# PocketBeagle.net
KiCad netlist of a schematic drawn in EAGLE
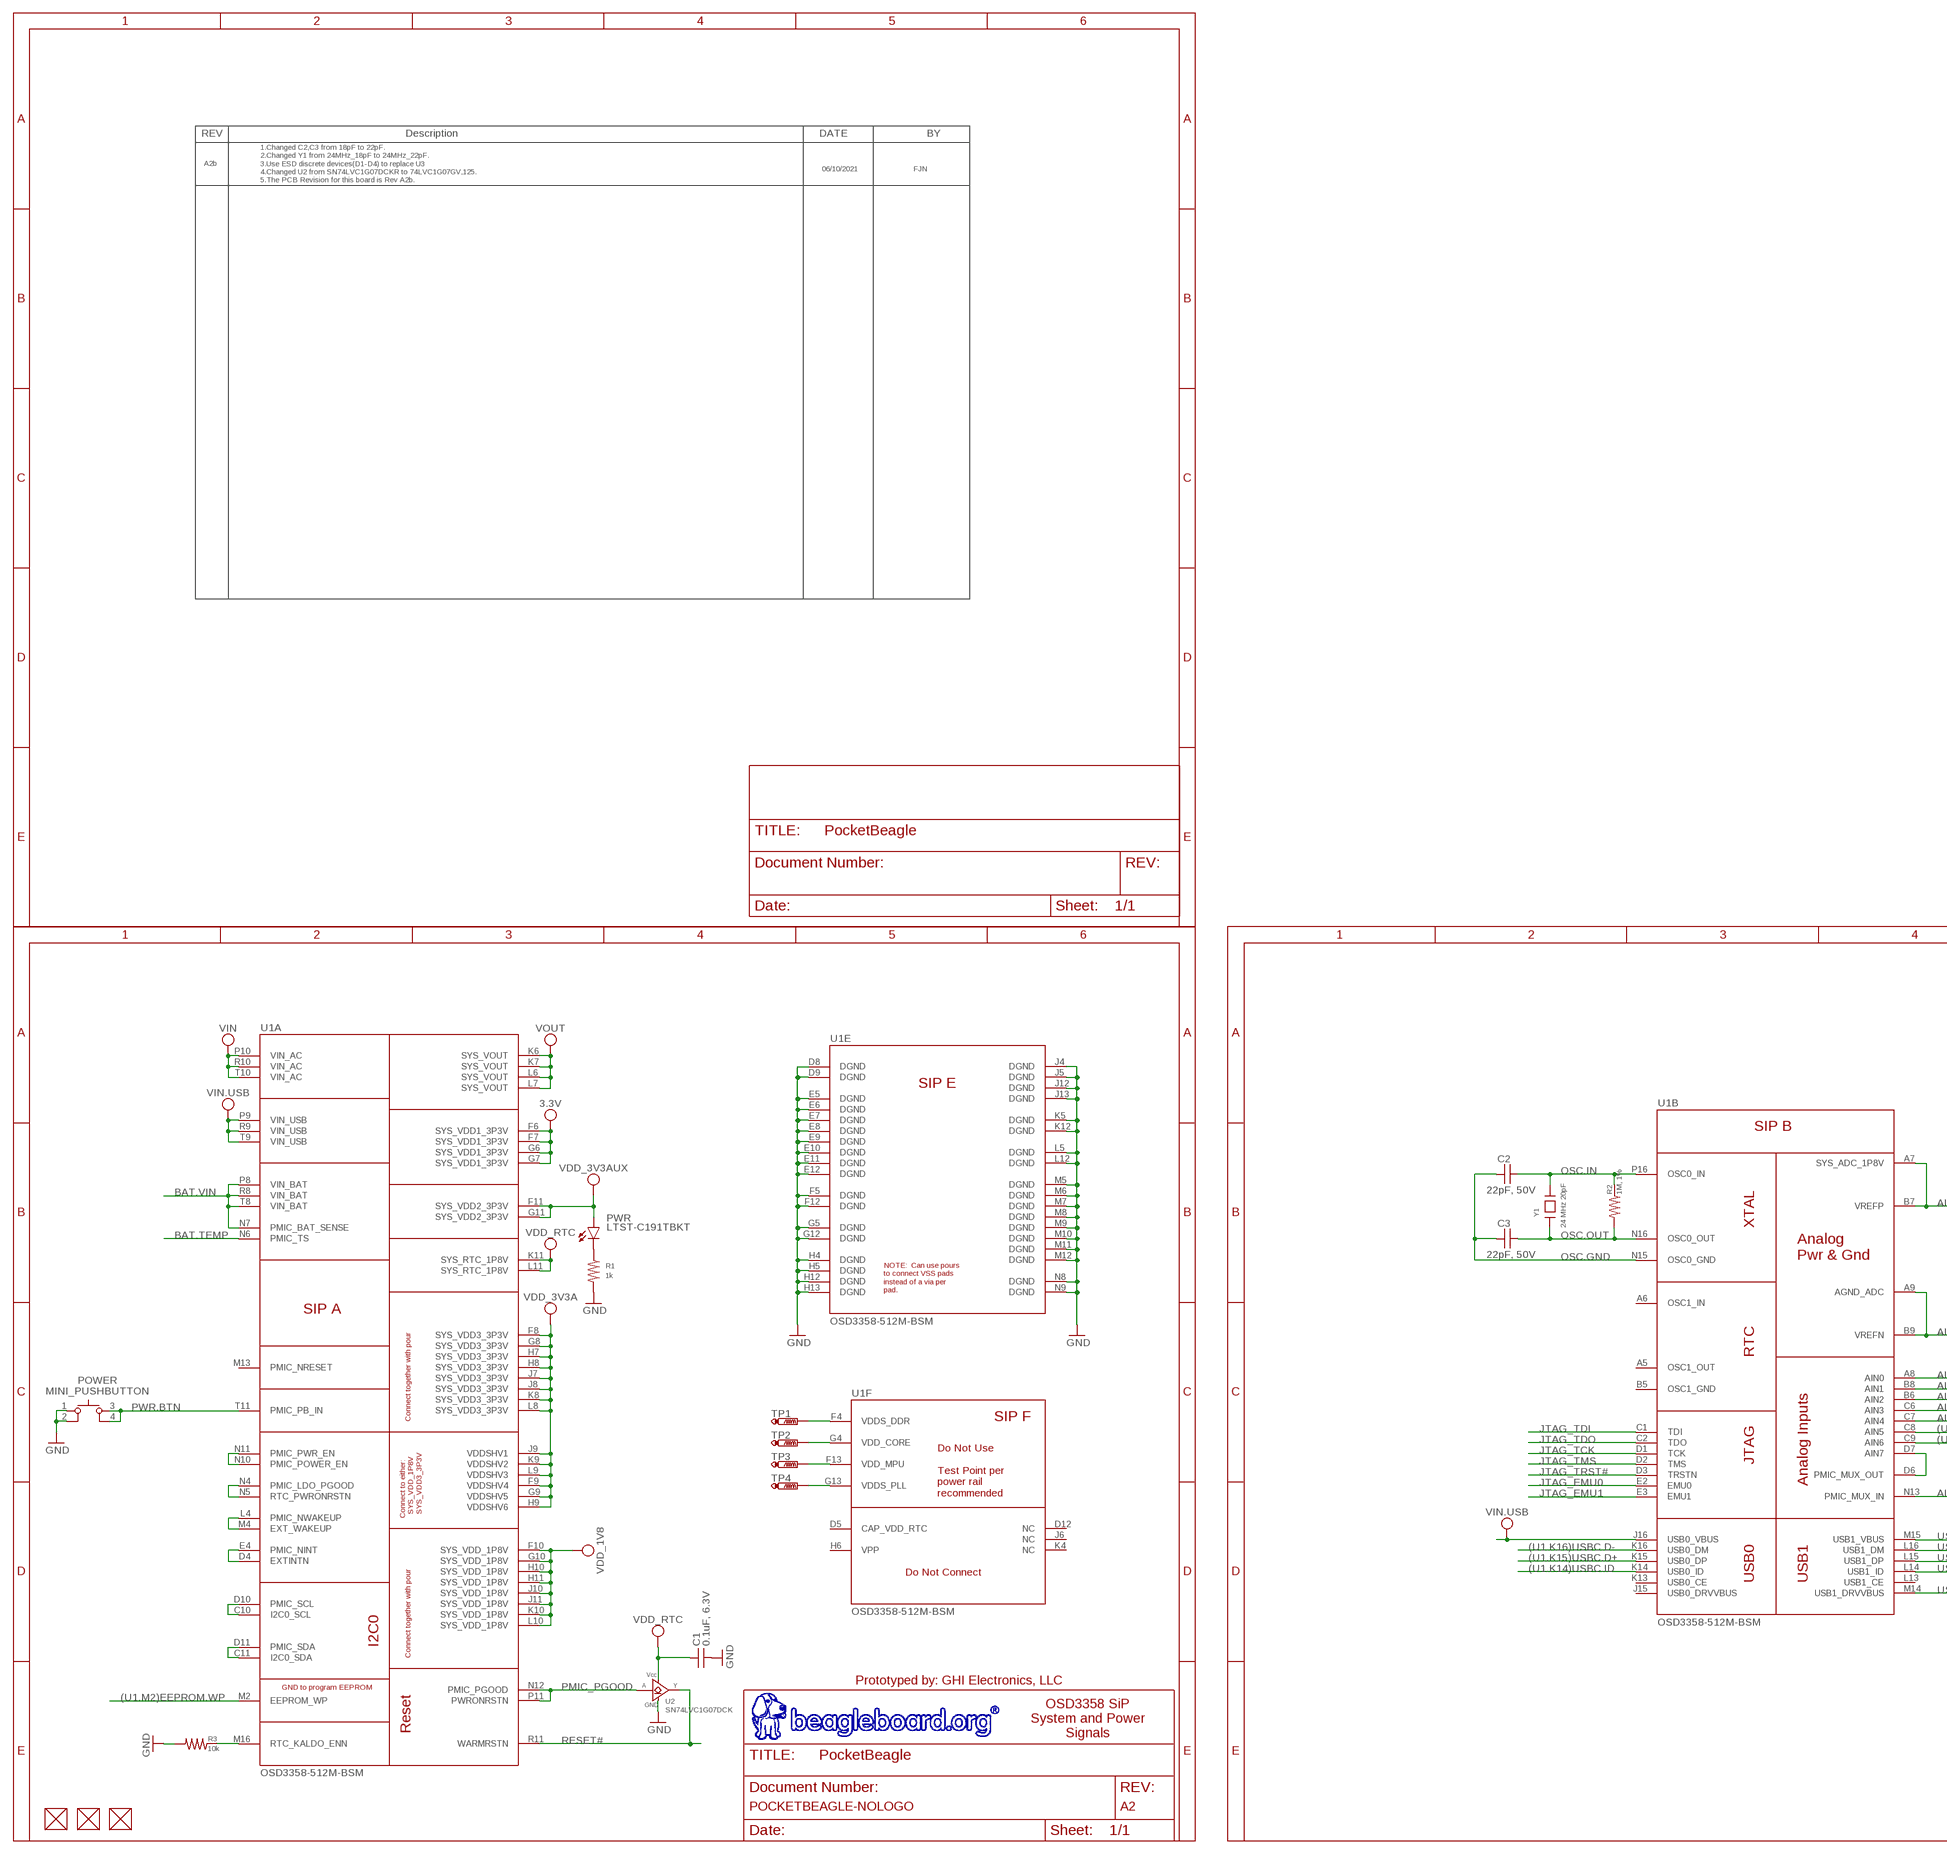
[diagram p0: schematic, sheet 1, part 1 of 3]
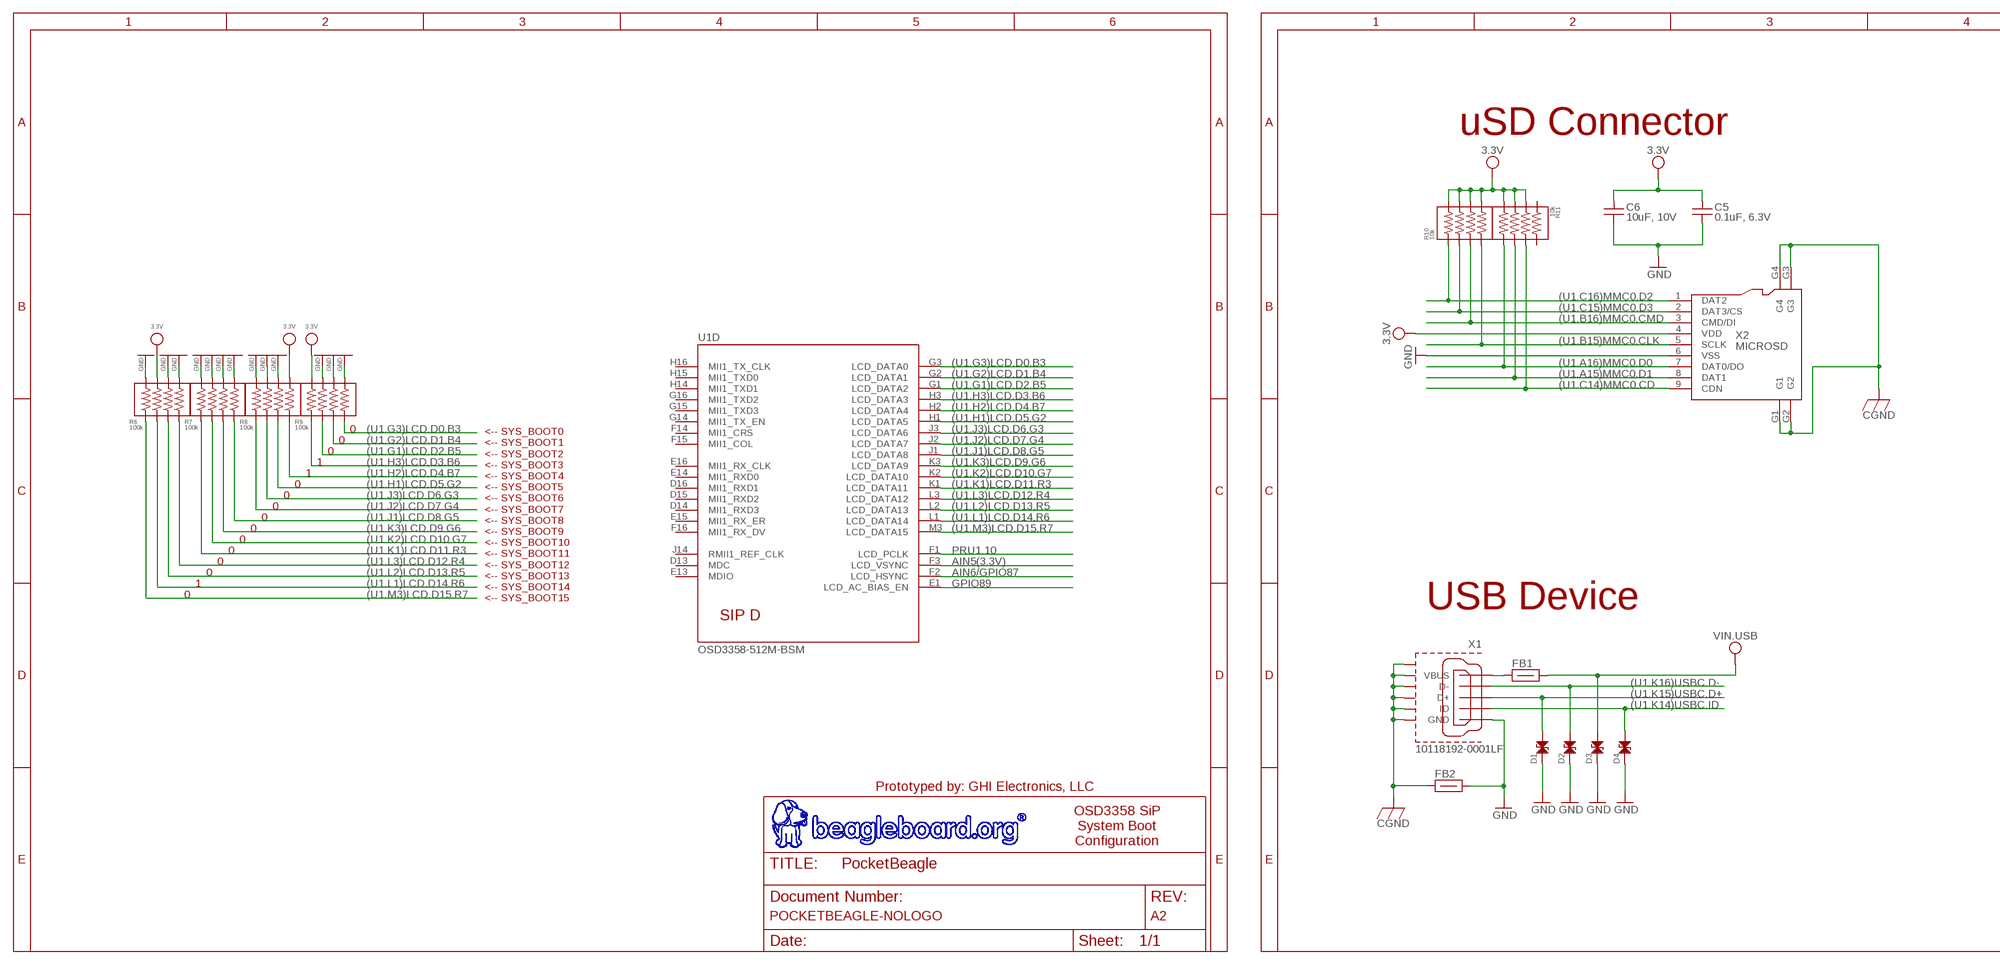
[diagram p1: schematic, sheet 1, part 2 of 3]
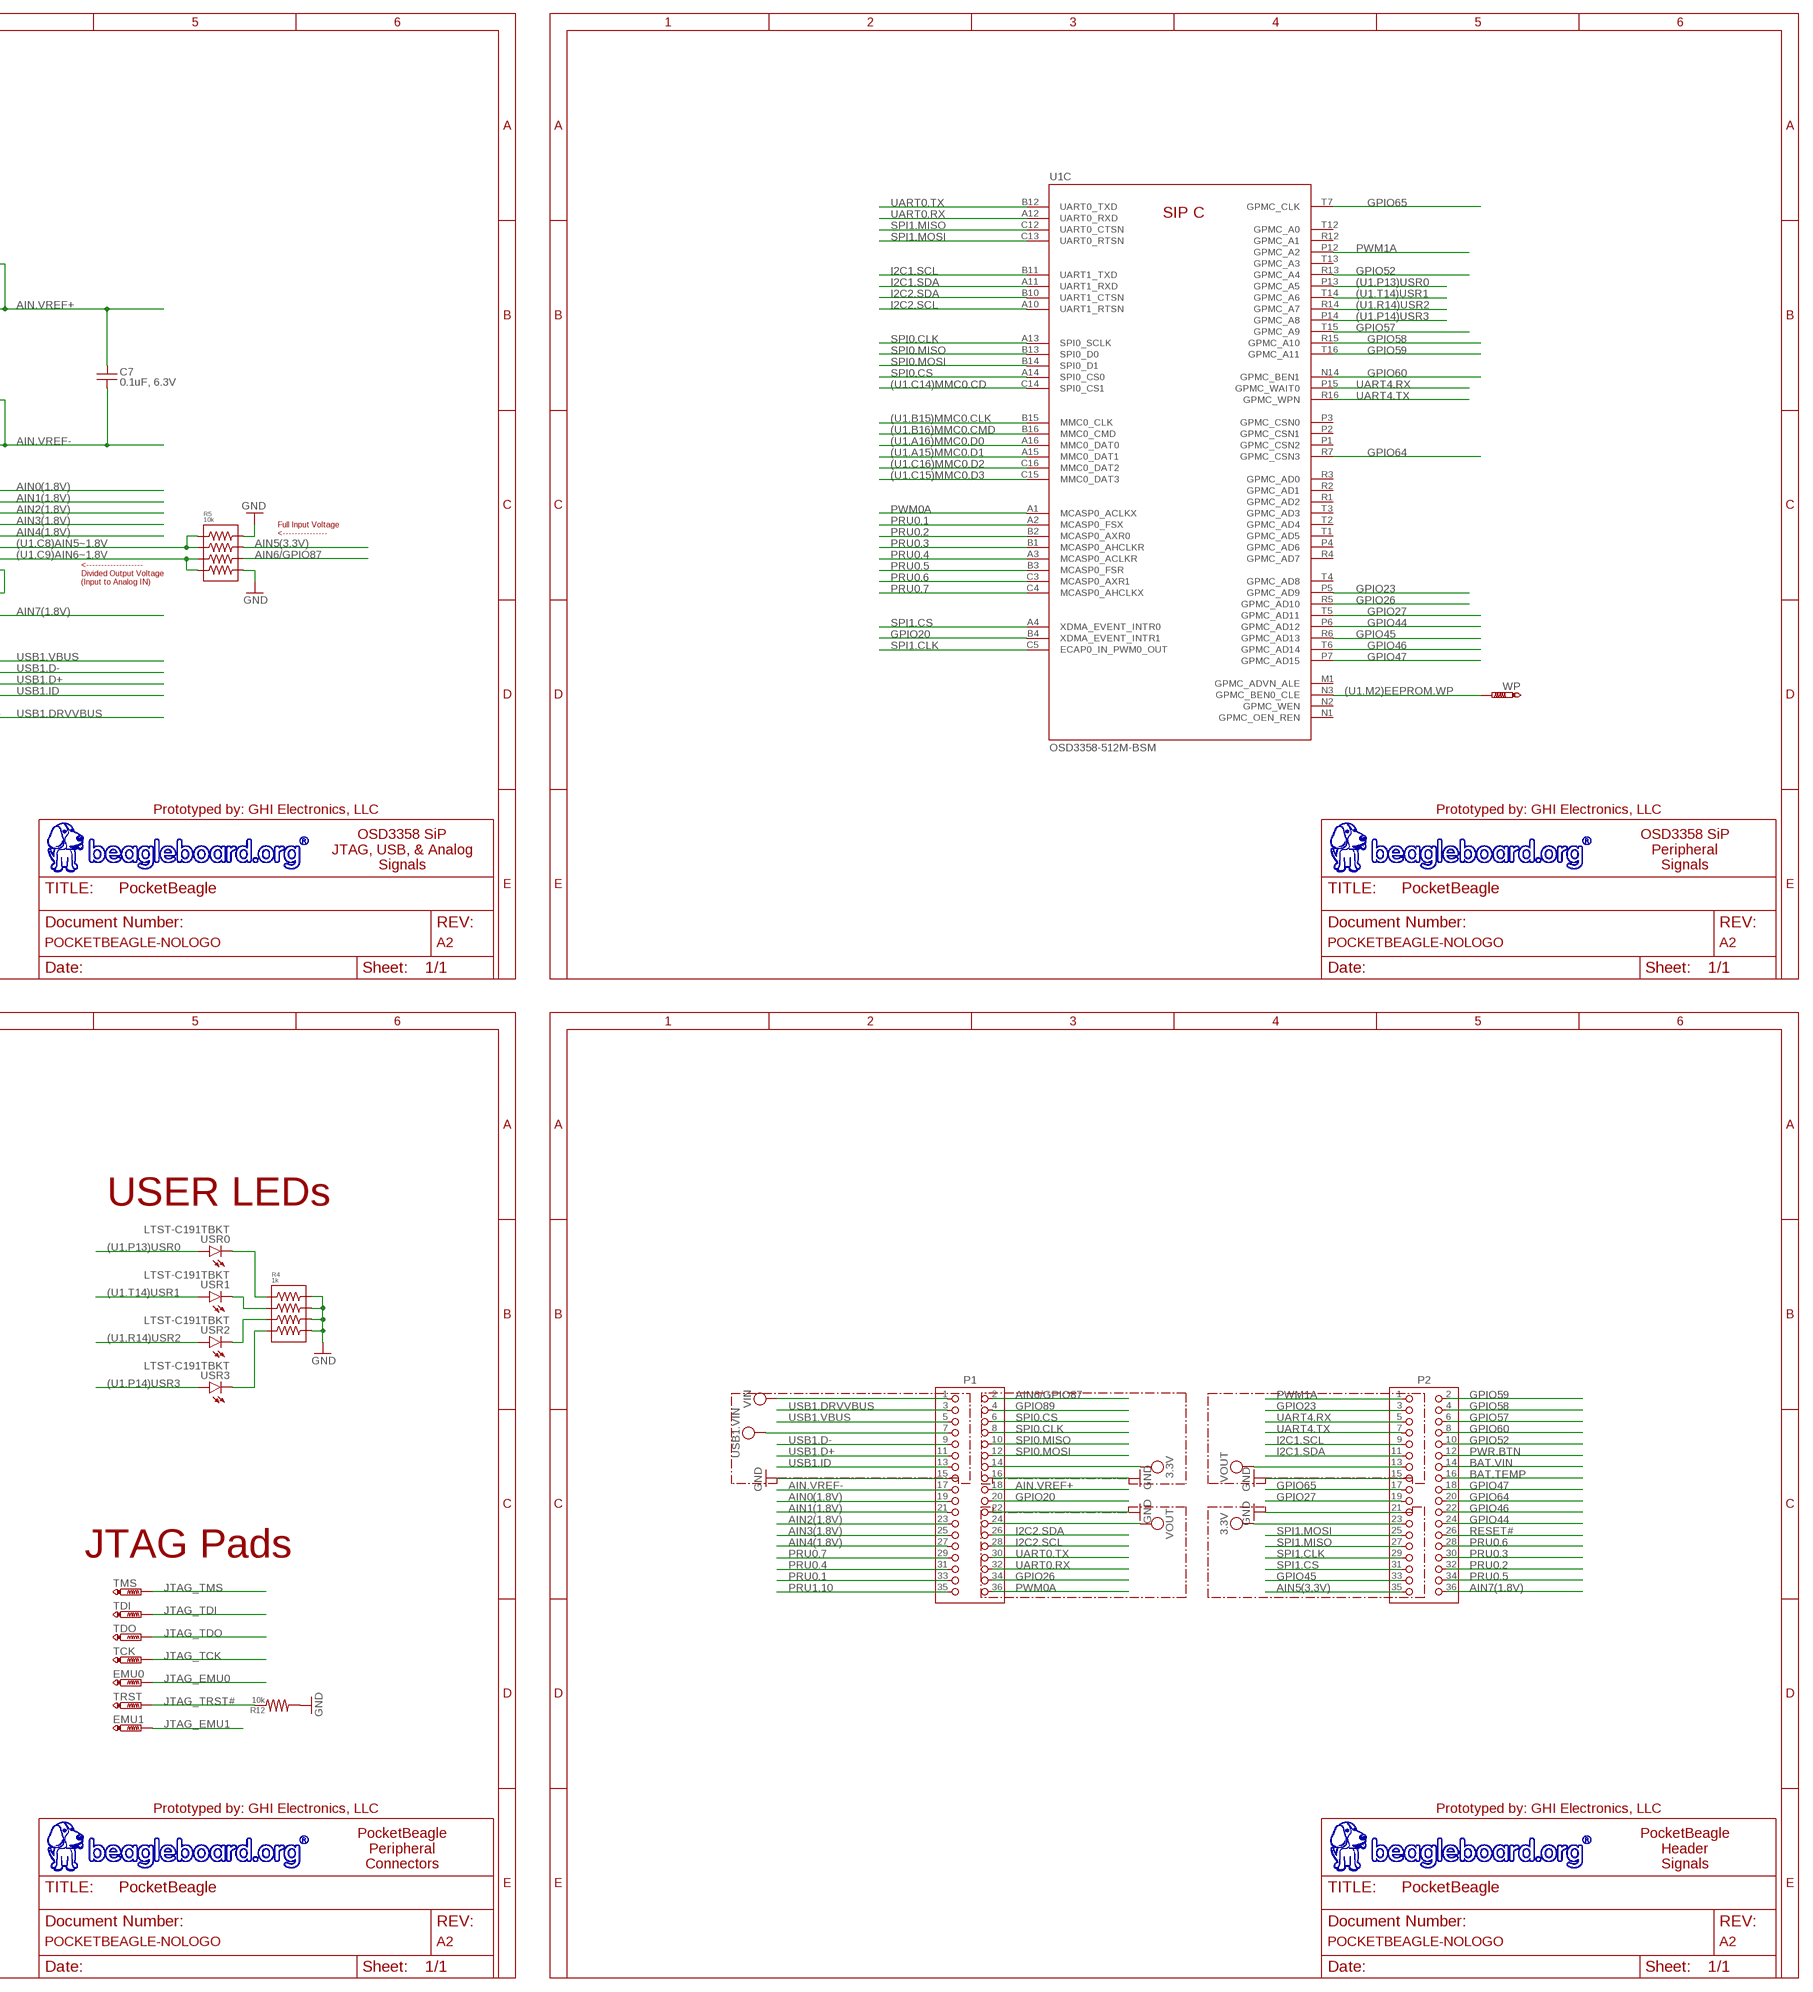
[diagram p2: schematic, sheet 1, part 3 of 3]

(export (version "E")
  (design (tool "Eeschema 10.0.6"))
  (components
    (comp (ref "C1")
      (value "0.1uF, 6.3V")
      (footprint "eagle-import:0402")
      (libsource (lib "eagle-import") (part "CAPACITOR-(INCH)-0402"))
    )
    (comp (ref "C2")
      (value "22pF, 50V")
      (footprint "eagle-import:0402")
      (libsource (lib "eagle-import") (part "CAPACITOR-(INCH)-0402"))
    )
    (comp (ref "C3")
      (value "22pF, 50V")
      (footprint "eagle-import:0402")
      (libsource (lib "eagle-import") (part "CAPACITOR-(INCH)-0402"))
    )
    (comp (ref "C5")
      (value "0.1uF, 6.3V")
      (footprint "eagle-import:0402")
      (libsource (lib "eagle-import") (part "CAPACITOR-(INCH)-0402"))
    )
    (comp (ref "C6")
      (value "10uF, 10V")
      (footprint "eagle-import:0603")
      (libsource (lib "eagle-import") (part "CAPACITOR-(INCH)-0603"))
    )
    (comp (ref "C7")
      (value "0.1uF, 6.3V")
      (footprint "eagle-import:0402")
      (libsource (lib "eagle-import") (part "CAPACITOR-(INCH)-0402"))
    )
    (comp (ref "D1")
      (value "D-ESD-2P-DOUBLE")
      (footprint "eagle-import:ESD-0402-NO-SILK")
      (libsource (lib "eagle-import") (part "D-ESD-2P-DOUBLE"))
    )
    (comp (ref "D2")
      (value "D-ESD-2P-DOUBLE")
      (footprint "eagle-import:ESD-0402-NO-SILK")
      (libsource (lib "eagle-import") (part "D-ESD-2P-DOUBLE"))
    )
    (comp (ref "D3")
      (value "D-ESD-2P-DOUBLE")
      (footprint "eagle-import:ESD-0402-NO-SILK")
      (libsource (lib "eagle-import") (part "D-ESD-2P-DOUBLE"))
    )
    (comp (ref "D4")
      (value "D-ESD-2P-DOUBLE")
      (footprint "eagle-import:ESD-0402-NO-SILK")
      (libsource (lib "eagle-import") (part "D-ESD-2P-DOUBLE"))
    )
    (comp (ref "EMU0")
      (value "PTR1B1,27")
      (footprint "eagle-import:B1,27")
      (libsource (lib "eagle-import") (part "PTR1B1,27"))
    )
    (comp (ref "EMU1")
      (value "PTR1B1,27")
      (footprint "eagle-import:B1,27")
      (libsource (lib "eagle-import") (part "PTR1B1,27"))
    )
    (comp (ref "FB1")
      (value "FB-(INCH)-0603")
      (footprint "eagle-import:0603")
      (libsource (lib "eagle-import") (part "FB-(INCH)-0603"))
    )
    (comp (ref "FB2")
      (value "FB-(INCH)-0603")
      (footprint "eagle-import:0603")
      (libsource (lib "eagle-import") (part "FB-(INCH)-0603"))
    )
    (comp (ref "FUD1")
      (value "FIDUCIAL")
      (footprint "eagle-import:FIDUCIAL_40MIL")
      (libsource (lib "eagle-import") (part "FIDUCIAL"))
    )
    (comp (ref "FUD2")
      (value "FIDUCIAL")
      (footprint "eagle-import:FIDUCIAL_40MIL")
      (libsource (lib "eagle-import") (part "FIDUCIAL"))
    )
    (comp (ref "FUD3")
      (value "FIDUCIAL")
      (footprint "eagle-import:FIDUCIAL_40MIL")
      (libsource (lib "eagle-import") (part "FIDUCIAL"))
    )
    (comp (ref "P1")
      (value "2X18-(INCH)-0.1-TH-(35MIL-DIA)-W/O-SILK")
      (footprint "eagle-import:TH-2X18-(35MIL-DIA)-W_O-SILK")
      (libsource (lib "eagle-import") (part "2X18-(INCH)-0.1-TH-(35MIL-DIA)-W/O-SILK"))
    )
    (comp (ref "P2")
      (value "2X18-(INCH)-0.1-TH-(35MIL-DIA)-W/O-SILK")
      (footprint "eagle-import:TH-2X18-(35MIL-DIA)-W_O-SILK")
      (libsource (lib "eagle-import") (part "2X18-(INCH)-0.1-TH-(35MIL-DIA)-W/O-SILK"))
    )
    (comp (ref "POWER")
      (value "MINI_PUSHBUTTON")
      (footprint "eagle-import:MINI_PUSHBUTTON")
      (libsource (lib "eagle-import") (part "MINI_PUSHBUTTON"))
    )
    (comp (ref "PWR")
      (value "LTST-C191TBKT")
      (footprint "eagle-import:0603-LED")
      (libsource (lib "eagle-import") (part "LED-(INCH)-0603"))
    )
    (comp (ref "R1")
      (value "1k")
      (footprint "eagle-import:0402")
      (libsource (lib "eagle-import") (part "RESISTOR-(INCH)-0402"))
    )
    (comp (ref "R2")
      (value "1M, 1%")
      (footprint "eagle-import:0402")
      (libsource (lib "eagle-import") (part "RESISTOR-(INCH)-0402"))
    )
    (comp (ref "R3")
      (value "10k")
      (footprint "eagle-import:0402")
      (libsource (lib "eagle-import") (part "RESISTOR-(INCH)-0402"))
    )
    (comp (ref "R4")
      (value "1k")
      (footprint "eagle-import:RN0804")
      (libsource (lib "eagle-import") (part "RESISTOR.NETWORK-(4)"))
    )
    (comp (ref "R5")
      (value "10k")
      (footprint "eagle-import:RN0804")
      (libsource (lib "eagle-import") (part "RESISTOR.NETWORK-(4)"))
    )
    (comp (ref "R6")
      (value "100k")
      (footprint "eagle-import:RN0804")
      (libsource (lib "eagle-import") (part "RESISTOR.NETWORK-(4)"))
    )
    (comp (ref "R7")
      (value "100k")
      (footprint "eagle-import:RN0804")
      (libsource (lib "eagle-import") (part "RESISTOR.NETWORK-(4)"))
    )
    (comp (ref "R8")
      (value "100k")
      (footprint "eagle-import:RN0804")
      (libsource (lib "eagle-import") (part "RESISTOR.NETWORK-(4)"))
    )
    (comp (ref "R9")
      (value "100k")
      (footprint "eagle-import:RN0804")
      (libsource (lib "eagle-import") (part "RESISTOR.NETWORK-(4)"))
    )
    (comp (ref "R10")
      (value "10k")
      (footprint "eagle-import:RN0804")
      (libsource (lib "eagle-import") (part "RESISTOR.NETWORK-(4)"))
    )
    (comp (ref "R11")
      (value "10k")
      (footprint "eagle-import:RN0804")
      (libsource (lib "eagle-import") (part "RESISTOR.NETWORK-(4)"))
    )
    (comp (ref "R12")
      (value "10k")
      (footprint "eagle-import:0402")
      (libsource (lib "eagle-import") (part "RESISTOR-(INCH)-0402"))
    )
    (comp (ref "TCK")
      (value "PTR1B1,27")
      (footprint "eagle-import:B1,27")
      (libsource (lib "eagle-import") (part "PTR1B1,27"))
    )
    (comp (ref "TDI")
      (value "PTR1B1,27")
      (footprint "eagle-import:B1,27")
      (libsource (lib "eagle-import") (part "PTR1B1,27"))
    )
    (comp (ref "TDO")
      (value "PTR1B1,27")
      (footprint "eagle-import:B1,27")
      (libsource (lib "eagle-import") (part "PTR1B1,27"))
    )
    (comp (ref "TMS")
      (value "PTR1B1,27")
      (footprint "eagle-import:B1,27")
      (libsource (lib "eagle-import") (part "PTR1B1,27"))
    )
    (comp (ref "TP1")
      (value "PTR1B1,27")
      (footprint "eagle-import:B1,27")
      (libsource (lib "eagle-import") (part "PTR1B1,27"))
    )
    (comp (ref "TP2")
      (value "PTR1B1,27")
      (footprint "eagle-import:B1,27")
      (libsource (lib "eagle-import") (part "PTR1B1,27"))
    )
    (comp (ref "TP3")
      (value "PTR1B1,27")
      (footprint "eagle-import:B1,27")
      (libsource (lib "eagle-import") (part "PTR1B1,27"))
    )
    (comp (ref "TP4")
      (value "PTR1B1,27")
      (footprint "eagle-import:B1,27")
      (libsource (lib "eagle-import") (part "PTR1B1,27"))
    )
    (comp (ref "TRST")
      (value "PTR1B1,27")
      (footprint "eagle-import:B1,27")
      (libsource (lib "eagle-import") (part "PTR1B1,27"))
    )
    (comp (ref "U1")
      (value "OSD3358-512M-BSM")
      (footprint "eagle-import:OSD335X-BGA-256")
      (libsource (lib "eagle-import") (part "OSD3358-512M-BSM"))
    )
    (comp (ref "U2")
      (value "SN74LVC1G07DCK")
      (footprint "eagle-import:SC70(TI-DCK)")
      (libsource (lib "eagle-import") (part "SN74LVC1G07DCK"))
    )
    (comp (ref "USR0")
      (value "LTST-C191TBKT")
      (footprint "eagle-import:0603-LED")
      (libsource (lib "eagle-import") (part "LED-(INCH)-0603"))
    )
    (comp (ref "USR1")
      (value "LTST-C191TBKT")
      (footprint "eagle-import:0603-LED")
      (libsource (lib "eagle-import") (part "LED-(INCH)-0603"))
    )
    (comp (ref "USR2")
      (value "LTST-C191TBKT")
      (footprint "eagle-import:0603-LED")
      (libsource (lib "eagle-import") (part "LED-(INCH)-0603"))
    )
    (comp (ref "USR3")
      (value "LTST-C191TBKT")
      (footprint "eagle-import:0603-LED")
      (libsource (lib "eagle-import") (part "LED-(INCH)-0603"))
    )
    (comp (ref "WP")
      (value "PTR1B1,27")
      (footprint "eagle-import:B1,27")
      (libsource (lib "eagle-import") (part "PTR1B1,27"))
    )
    (comp (ref "X1")
      (value "10118192-0001LF")
      (footprint "eagle-import:10118192-0001LF(MICRO-USB-B-AMPHENOL-FCI)")
      (libsource (lib "eagle-import") (part "10118192-0001LF"))
    )
    (comp (ref "X2")
      (value "MICROSD")
      (footprint "eagle-import:MICROSD")
      (libsource (lib "eagle-import") (part "MICROSD"))
    )
    (comp (ref "Y1")
      (value "24 MHz 20pF")
      (footprint "eagle-import:CRYSTAL_5X3.2MM")
      (libsource (lib "eagle-import") (part "CRYSTAL_5X3.2MM"))
    )
  )
  (nets
    (net (code "1") (name "/(U1.A15)MMC0.D1") (class "Default")
      (node (ref "R11") (pin "6") (pinfunction "6_6") (pintype "bidirectional"))
      (node (ref "U1") (pin "A15") (pinfunction "MMC0_DAT1_A15") (pintype "bidirectional"))
      (node (ref "X2") (pin "8") (pinfunction "DAT1_8") (pintype "bidirectional"))
    )
    (net (code "2") (name "/(U1.A16)MMC0.D0") (class "Default")
      (node (ref "R11") (pin "5") (pinfunction "5_5") (pintype "bidirectional"))
      (node (ref "U1") (pin "A16") (pinfunction "MMC0_DAT0_A16") (pintype "bidirectional"))
      (node (ref "X2") (pin "7") (pinfunction "DAT0/DO_7") (pintype "bidirectional"))
    )
    (net (code "3") (name "/(U1.B15)MMC0.CLK") (class "Default")
      (node (ref "R10") (pin "4") (pinfunction "4_4") (pintype "bidirectional"))
      (node (ref "U1") (pin "B15") (pinfunction "MMC0_CLK_B15") (pintype "bidirectional"))
      (node (ref "X2") (pin "5") (pinfunction "SCLK_5") (pintype "bidirectional"))
    )
    (net (code "4") (name "/(U1.B16)MMC0.CMD") (class "Default")
      (node (ref "R10") (pin "3") (pinfunction "3_3") (pintype "bidirectional"))
      (node (ref "U1") (pin "B16") (pinfunction "MMC0_CMD_B16") (pintype "bidirectional"))
      (node (ref "X2") (pin "3") (pinfunction "CMD/DI_3") (pintype "bidirectional"))
    )
    (net (code "5") (name "/(U1.C8)AIN5~{1.8V}") (class "Default")
      (node (ref "R5") (pin "1") (pinfunction "1_1") (pintype "bidirectional"))
      (node (ref "R5") (pin "2") (pinfunction "2_2") (pintype "bidirectional"))
      (node (ref "U1") (pin "C8") (pinfunction "AIN5_C8") (pintype "bidirectional"))
    )
    (net (code "6") (name "/(U1.C9)AIN6~{1.8V}") (class "Default")
      (node (ref "R5") (pin "3") (pinfunction "3_3") (pintype "bidirectional"))
      (node (ref "R5") (pin "4") (pinfunction "4_4") (pintype "bidirectional"))
      (node (ref "U1") (pin "C9") (pinfunction "AIN6_C9") (pintype "bidirectional"))
    )
    (net (code "7") (name "/(U1.C14)MMC0.CD") (class "Default")
      (node (ref "R11") (pin "7") (pinfunction "7_7") (pintype "bidirectional"))
      (node (ref "U1") (pin "C14") (pinfunction "SPI0_CS1_C14") (pintype "bidirectional"))
      (node (ref "X2") (pin "9") (pinfunction "CDN_9") (pintype "bidirectional"))
    )
    (net (code "8") (name "/(U1.C15)MMC0.D3") (class "Default")
      (node (ref "R10") (pin "2") (pinfunction "2_2") (pintype "bidirectional"))
      (node (ref "U1") (pin "C15") (pinfunction "MMC0_DAT3_C15") (pintype "bidirectional"))
      (node (ref "X2") (pin "2") (pinfunction "DAT3/CS_2") (pintype "bidirectional"))
    )
    (net (code "9") (name "/(U1.C16)MMC0.D2") (class "Default")
      (node (ref "R10") (pin "1") (pinfunction "1_1") (pintype "bidirectional"))
      (node (ref "U1") (pin "C16") (pinfunction "MMC0_DAT2_C16") (pintype "bidirectional"))
      (node (ref "X2") (pin "1") (pinfunction "DAT2_1") (pintype "bidirectional"))
    )
    (net (code "10") (name "/(U1.G1)LCD.D2.B5") (class "Default")
      (node (ref "R9") (pin "6") (pinfunction "6_6") (pintype "bidirectional"))
      (node (ref "U1") (pin "G1") (pinfunction "LCD_DATA2_G1") (pintype "bidirectional"))
    )
    (net (code "11") (name "/(U1.G2)LCD.D1.B4") (class "Default")
      (node (ref "R9") (pin "7") (pinfunction "7_7") (pintype "bidirectional"))
      (node (ref "U1") (pin "G2") (pinfunction "LCD_DATA1_G2") (pintype "bidirectional"))
    )
    (net (code "12") (name "/(U1.G3)LCD.D0.B3") (class "Default")
      (node (ref "R9") (pin "8") (pinfunction "8_8") (pintype "bidirectional"))
      (node (ref "U1") (pin "G3") (pinfunction "LCD_DATA0_G3") (pintype "bidirectional"))
    )
    (net (code "13") (name "/(U1.H1)LCD.D5.G2") (class "Default")
      (node (ref "R8") (pin "3") (pinfunction "3_3") (pintype "bidirectional"))
      (node (ref "U1") (pin "H1") (pinfunction "LCD_DATA5_H1") (pintype "bidirectional"))
    )
    (net (code "14") (name "/(U1.H2)LCD.D4.B7") (class "Default")
      (node (ref "R8") (pin "4") (pinfunction "4_4") (pintype "bidirectional"))
      (node (ref "U1") (pin "H2") (pinfunction "LCD_DATA4_H2") (pintype "bidirectional"))
    )
    (net (code "15") (name "/(U1.H3)LCD.D3.B6") (class "Default")
      (node (ref "R9") (pin "5") (pinfunction "5_5") (pintype "bidirectional"))
      (node (ref "U1") (pin "H3") (pinfunction "LCD_DATA3_H3") (pintype "bidirectional"))
    )
    (net (code "16") (name "/(U1.J1)LCD.D8.G5") (class "Default")
      (node (ref "R7") (pin "4") (pinfunction "4_4") (pintype "bidirectional"))
      (node (ref "U1") (pin "J1") (pinfunction "LCD_DATA8_J1") (pintype "bidirectional"))
    )
    (net (code "17") (name "/(U1.J2)LCD.D7.G4") (class "Default")
      (node (ref "R8") (pin "1") (pinfunction "1_1") (pintype "bidirectional"))
      (node (ref "U1") (pin "J2") (pinfunction "LCD_DATA7_J2") (pintype "bidirectional"))
    )
    (net (code "18") (name "/(U1.J3)LCD.D6.G3") (class "Default")
      (node (ref "R8") (pin "2") (pinfunction "2_2") (pintype "bidirectional"))
      (node (ref "U1") (pin "J3") (pinfunction "LCD_DATA6_J3") (pintype "bidirectional"))
    )
    (net (code "19") (name "/(U1.K1)LCD.D11.R3") (class "Default")
      (node (ref "R7") (pin "1") (pinfunction "1_1") (pintype "bidirectional"))
      (node (ref "U1") (pin "K1") (pinfunction "LCD_DATA11_K1") (pintype "bidirectional"))
    )
    (net (code "20") (name "/(U1.K2)LCD.D10.G7") (class "Default")
      (node (ref "R7") (pin "2") (pinfunction "2_2") (pintype "bidirectional"))
      (node (ref "U1") (pin "K2") (pinfunction "LCD_DATA10_K2") (pintype "bidirectional"))
    )
    (net (code "21") (name "/(U1.K3)LCD.D9.G6") (class "Default")
      (node (ref "R7") (pin "3") (pinfunction "3_3") (pintype "bidirectional"))
      (node (ref "U1") (pin "K3") (pinfunction "LCD_DATA9_K3") (pintype "bidirectional"))
    )
    (net (code "22") (name "/(U1.K14)USBC.ID") (class "Default")
      (node (ref "D4") (pin "2") (pinfunction "2_2") (pintype "bidirectional"))
      (node (ref "U1") (pin "K14") (pinfunction "USB0_ID_K14") (pintype "bidirectional"))
      (node (ref "X1") (pin "ID") (pinfunction "ID_ID") (pintype "input"))
    )
    (net (code "23") (name "/(U1.K15)USBC.D+") (class "Default")
      (node (ref "D1") (pin "2") (pinfunction "2_2") (pintype "bidirectional"))
      (node (ref "U1") (pin "K15") (pinfunction "USB0_DP_K15") (pintype "bidirectional"))
      (node (ref "X1") (pin "D+") (pinfunction "D+_D+") (pintype "input"))
    )
    (net (code "24") (name "/(U1.K16)USBC.D-") (class "Default")
      (node (ref "D2") (pin "2") (pinfunction "2_2") (pintype "bidirectional"))
      (node (ref "U1") (pin "K16") (pinfunction "USB0_DM_K16") (pintype "bidirectional"))
      (node (ref "X1") (pin "D-") (pinfunction "D-_D-") (pintype "input"))
    )
    (net (code "25") (name "/(U1.L1)LCD.D14.R6") (class "Default")
      (node (ref "R6") (pin "2") (pinfunction "2_2") (pintype "bidirectional"))
      (node (ref "U1") (pin "L1") (pinfunction "LCD_DATA14_L1") (pintype "bidirectional"))
    )
    (net (code "26") (name "/(U1.L2)LCD.D13.R5") (class "Default")
      (node (ref "R6") (pin "3") (pinfunction "3_3") (pintype "bidirectional"))
      (node (ref "U1") (pin "L2") (pinfunction "LCD_DATA13_L2") (pintype "bidirectional"))
    )
    (net (code "27") (name "/(U1.L3)LCD.D12.R4") (class "Default")
      (node (ref "R6") (pin "4") (pinfunction "4_4") (pintype "bidirectional"))
      (node (ref "U1") (pin "L3") (pinfunction "LCD_DATA12_L3") (pintype "bidirectional"))
    )
    (net (code "28") (name "/(U1.M2)EEPROM.WP") (class "Default")
      (node (ref "U1") (pin "M2") (pinfunction "EEPROM_WP_M2") (pintype "bidirectional"))
      (node (ref "U1") (pin "N3") (pinfunction "GPMC_BEN0_CLE_N3") (pintype "bidirectional"))
      (node (ref "WP") (pin "TP") (pinfunction "TP_TP") (pintype "input"))
    )
    (net (code "29") (name "/(U1.M3)LCD.D15.R7") (class "Default")
      (node (ref "R6") (pin "1") (pinfunction "1_1") (pintype "bidirectional"))
      (node (ref "U1") (pin "M3") (pinfunction "LCD_DATA15_M3") (pintype "bidirectional"))
    )
    (net (code "30") (name "/(U1.P13)USR0") (class "Default")
      (node (ref "U1") (pin "P13") (pinfunction "GPMC_A5_P13") (pintype "bidirectional"))
      (node (ref "USR0") (pin "A") (pinfunction "A_A") (pintype "passive"))
    )
    (net (code "31") (name "/(U1.P14)USR3") (class "Default")
      (node (ref "U1") (pin "P14") (pinfunction "GPMC_A8_P14") (pintype "bidirectional"))
      (node (ref "USR3") (pin "A") (pinfunction "A_A") (pintype "passive"))
    )
    (net (code "32") (name "/(U1.R14)USR2") (class "Default")
      (node (ref "U1") (pin "R14") (pinfunction "GPMC_A7_R14") (pintype "bidirectional"))
      (node (ref "USR2") (pin "A") (pinfunction "A_A") (pintype "passive"))
    )
    (net (code "33") (name "/(U1.T14)USR1") (class "Default")
      (node (ref "U1") (pin "T14") (pinfunction "GPMC_A6_T14") (pintype "bidirectional"))
      (node (ref "USR1") (pin "A") (pinfunction "A_A") (pintype "passive"))
    )
    (net (code "34") (name "/AIN.VREF+") (class "Default")
      (node (ref "C7") (pin "1") (pinfunction "1_1") (pintype "bidirectional"))
      (node (ref "P1") (pin "18") (pinfunction "18_18") (pintype "bidirectional"))
      (node (ref "U1") (pin "A7") (pinfunction "SYS_ADC_1P8V_A7") (pintype "bidirectional"))
      (node (ref "U1") (pin "B7") (pinfunction "VREFP_B7") (pintype "bidirectional"))
    )
    (net (code "35") (name "/AIN.VREF-") (class "Default")
      (node (ref "C7") (pin "2") (pinfunction "2_2") (pintype "bidirectional"))
      (node (ref "P1") (pin "17") (pinfunction "17_17") (pintype "bidirectional"))
      (node (ref "U1") (pin "A9") (pinfunction "AGND_ADC_A9") (pintype "bidirectional"))
      (node (ref "U1") (pin "B9") (pinfunction "VREFN_B9") (pintype "bidirectional"))
    )
    (net (code "36") (name "/AIN0(1.8V)") (class "Default")
      (node (ref "P1") (pin "19") (pinfunction "19_19") (pintype "bidirectional"))
      (node (ref "U1") (pin "A8") (pinfunction "AIN0_A8") (pintype "bidirectional"))
    )
    (net (code "37") (name "/AIN1(1.8V)") (class "Default")
      (node (ref "P1") (pin "21") (pinfunction "21_21") (pintype "bidirectional"))
      (node (ref "U1") (pin "B8") (pinfunction "AIN1_B8") (pintype "bidirectional"))
    )
    (net (code "38") (name "/AIN2(1.8V)") (class "Default")
      (node (ref "P1") (pin "23") (pinfunction "23_23") (pintype "bidirectional"))
      (node (ref "U1") (pin "B6") (pinfunction "AIN2_B6") (pintype "bidirectional"))
    )
    (net (code "39") (name "/AIN3(1.8V)") (class "Default")
      (node (ref "P1") (pin "25") (pinfunction "25_25") (pintype "bidirectional"))
      (node (ref "U1") (pin "C6") (pinfunction "AIN3_C6") (pintype "bidirectional"))
    )
    (net (code "40") (name "/AIN4(1.8V)") (class "Default")
      (node (ref "P1") (pin "27") (pinfunction "27_27") (pintype "bidirectional"))
      (node (ref "U1") (pin "C7") (pinfunction "AIN4_C7") (pintype "bidirectional"))
    )
    (net (code "41") (name "/AIN5(3.3V)") (class "Default")
      (node (ref "P2") (pin "35") (pinfunction "35_35") (pintype "bidirectional"))
      (node (ref "R5") (pin "7") (pinfunction "7_7") (pintype "bidirectional"))
      (node (ref "U1") (pin "F3") (pinfunction "LCD_VSYNC_F3") (pintype "bidirectional"))
    )
    (net (code "42") (name "/AIN6{slash}GPIO87") (class "Default")
      (node (ref "P1") (pin "2") (pinfunction "2_2") (pintype "bidirectional"))
      (node (ref "R5") (pin "6") (pinfunction "6_6") (pintype "bidirectional"))
      (node (ref "U1") (pin "F2") (pinfunction "LCD_HSYNC_F2") (pintype "bidirectional"))
    )
    (net (code "43") (name "/AIN7(1.8V)") (class "Default")
      (node (ref "P2") (pin "36") (pinfunction "36_36") (pintype "bidirectional"))
      (node (ref "U1") (pin "N13") (pinfunction "PMIC_MUX_IN_N13") (pintype "bidirectional"))
    )
    (net (code "44") (name "/BAT.TEMP") (class "Default")
      (node (ref "P2") (pin "16") (pinfunction "16_16") (pintype "bidirectional"))
      (node (ref "U1") (pin "N6") (pinfunction "PMIC_TS_N6") (pintype "bidirectional"))
    )
    (net (code "45") (name "/BAT.VIN") (class "Default")
      (node (ref "P2") (pin "14") (pinfunction "14_14") (pintype "bidirectional"))
      (node (ref "U1") (pin "N7") (pinfunction "PMIC_BAT_SENSE_N7") (pintype "bidirectional"))
      (node (ref "U1") (pin "P8") (pinfunction "VIN_BAT_P8") (pintype "power_in"))
      (node (ref "U1") (pin "R8") (pinfunction "VIN_BAT_R8") (pintype "power_in"))
      (node (ref "U1") (pin "T8") (pinfunction "VIN_BAT_T8") (pintype "power_in"))
    )
    (net (code "46") (name "/GPIO20") (class "Default")
      (node (ref "P1") (pin "20") (pinfunction "20_20") (pintype "bidirectional"))
      (node (ref "U1") (pin "B4") (pinfunction "XDMA_EVENT_INTR1_B4") (pintype "bidirectional"))
    )
    (net (code "47") (name "/GPIO23") (class "Default")
      (node (ref "P2") (pin "3") (pinfunction "3_3") (pintype "bidirectional"))
      (node (ref "U1") (pin "P5") (pinfunction "GPMC_AD9_P5") (pintype "bidirectional"))
    )
    (net (code "48") (name "/GPIO26") (class "Default")
      (node (ref "P1") (pin "34") (pinfunction "34_34") (pintype "bidirectional"))
      (node (ref "U1") (pin "R5") (pinfunction "GPMC_AD10_R5") (pintype "bidirectional"))
    )
    (net (code "49") (name "/GPIO27") (class "Default")
      (node (ref "P2") (pin "19") (pinfunction "19_19") (pintype "bidirectional"))
      (node (ref "U1") (pin "T5") (pinfunction "GPMC_AD11_T5") (pintype "bidirectional"))
    )
    (net (code "50") (name "/GPIO44") (class "Default")
      (node (ref "P2") (pin "24") (pinfunction "24_24") (pintype "bidirectional"))
      (node (ref "U1") (pin "P6") (pinfunction "GPMC_AD12_P6") (pintype "bidirectional"))
    )
    (net (code "51") (name "/GPIO45") (class "Default")
      (node (ref "P2") (pin "33") (pinfunction "33_33") (pintype "bidirectional"))
      (node (ref "U1") (pin "R6") (pinfunction "GPMC_AD13_R6") (pintype "bidirectional"))
    )
    (net (code "52") (name "/GPIO46") (class "Default")
      (node (ref "P2") (pin "22") (pinfunction "22_22") (pintype "bidirectional"))
      (node (ref "U1") (pin "T6") (pinfunction "GPMC_AD14_T6") (pintype "bidirectional"))
    )
    (net (code "53") (name "/GPIO47") (class "Default")
      (node (ref "P2") (pin "18") (pinfunction "18_18") (pintype "bidirectional"))
      (node (ref "U1") (pin "P7") (pinfunction "GPMC_AD15_P7") (pintype "bidirectional"))
    )
    (net (code "54") (name "/GPIO52") (class "Default")
      (node (ref "P2") (pin "10") (pinfunction "10_10") (pintype "bidirectional"))
      (node (ref "U1") (pin "R13") (pinfunction "GPMC_A4_R13") (pintype "bidirectional"))
    )
    (net (code "55") (name "/GPIO57") (class "Default")
      (node (ref "P2") (pin "6") (pinfunction "6_6") (pintype "bidirectional"))
      (node (ref "U1") (pin "T15") (pinfunction "GPMC_A9_T15") (pintype "bidirectional"))
    )
    (net (code "56") (name "/GPIO58") (class "Default")
      (node (ref "P2") (pin "4") (pinfunction "4_4") (pintype "bidirectional"))
      (node (ref "U1") (pin "R15") (pinfunction "GPMC_A10_R15") (pintype "bidirectional"))
    )
    (net (code "57") (name "/GPIO59") (class "Default")
      (node (ref "P2") (pin "2") (pinfunction "2_2") (pintype "bidirectional"))
      (node (ref "U1") (pin "T16") (pinfunction "GPMC_A11_T16") (pintype "bidirectional"))
    )
    (net (code "58") (name "/GPIO60") (class "Default")
      (node (ref "P2") (pin "8") (pinfunction "8_8") (pintype "bidirectional"))
      (node (ref "U1") (pin "N14") (pinfunction "GPMC_BEN1_N14") (pintype "bidirectional"))
    )
    (net (code "59") (name "/GPIO64") (class "Default")
      (node (ref "P2") (pin "20") (pinfunction "20_20") (pintype "bidirectional"))
      (node (ref "U1") (pin "R7") (pinfunction "GPMC_CSN3_R7") (pintype "bidirectional"))
    )
    (net (code "60") (name "/GPIO65") (class "Default")
      (node (ref "P2") (pin "17") (pinfunction "17_17") (pintype "bidirectional"))
      (node (ref "U1") (pin "T7") (pinfunction "GPMC_CLK_T7") (pintype "bidirectional"))
    )
    (net (code "61") (name "/GPIO89") (class "Default")
      (node (ref "P1") (pin "4") (pinfunction "4_4") (pintype "bidirectional"))
      (node (ref "U1") (pin "E1") (pinfunction "LCD_AC_BIAS_EN_E1") (pintype "bidirectional"))
    )
    (net (code "62") (name "/I2C1.SCL") (class "Default")
      (node (ref "P2") (pin "9") (pinfunction "9_9") (pintype "bidirectional"))
      (node (ref "U1") (pin "B11") (pinfunction "UART1_TXD_B11") (pintype "bidirectional"))
    )
    (net (code "63") (name "/I2C1.SDA") (class "Default")
      (node (ref "P2") (pin "11") (pinfunction "11_11") (pintype "bidirectional"))
      (node (ref "U1") (pin "A11") (pinfunction "UART1_RXD_A11") (pintype "bidirectional"))
    )
    (net (code "64") (name "/I2C2.SCL") (class "Default")
      (node (ref "P1") (pin "28") (pinfunction "28_28") (pintype "bidirectional"))
      (node (ref "U1") (pin "A10") (pinfunction "UART1_RTSN_A10") (pintype "bidirectional"))
    )
    (net (code "65") (name "/I2C2.SDA") (class "Default")
      (node (ref "P1") (pin "26") (pinfunction "26_26") (pintype "bidirectional"))
      (node (ref "U1") (pin "B10") (pinfunction "UART1_CTSN_B10") (pintype "bidirectional"))
    )
    (net (code "66") (name "/JTAG_EMU0") (class "Default")
      (node (ref "EMU0") (pin "TP") (pinfunction "TP_TP") (pintype "input"))
      (node (ref "U1") (pin "E2") (pinfunction "EMU0_E2") (pintype "bidirectional"))
    )
    (net (code "67") (name "/JTAG_EMU1") (class "Default")
      (node (ref "EMU1") (pin "TP") (pinfunction "TP_TP") (pintype "input"))
      (node (ref "U1") (pin "E3") (pinfunction "EMU1_E3") (pintype "bidirectional"))
    )
    (net (code "68") (name "/JTAG_TCK") (class "Default")
      (node (ref "TCK") (pin "TP") (pinfunction "TP_TP") (pintype "input"))
      (node (ref "U1") (pin "D1") (pinfunction "TCK_D1") (pintype "bidirectional"))
    )
    (net (code "69") (name "/JTAG_TDI") (class "Default")
      (node (ref "TDI") (pin "TP") (pinfunction "TP_TP") (pintype "input"))
      (node (ref "U1") (pin "C1") (pinfunction "TDI_C1") (pintype "bidirectional"))
    )
    (net (code "70") (name "/JTAG_TDO") (class "Default")
      (node (ref "TDO") (pin "TP") (pinfunction "TP_TP") (pintype "input"))
      (node (ref "U1") (pin "C2") (pinfunction "TDO_C2") (pintype "bidirectional"))
    )
    (net (code "71") (name "/JTAG_TMS") (class "Default")
      (node (ref "TMS") (pin "TP") (pinfunction "TP_TP") (pintype "input"))
      (node (ref "U1") (pin "D2") (pinfunction "TMS_D2") (pintype "bidirectional"))
    )
    (net (code "72") (name "/JTAG_TRST#") (class "Default")
      (node (ref "R12") (pin "2") (pinfunction "2_2") (pintype "bidirectional"))
      (node (ref "TRST") (pin "TP") (pinfunction "TP_TP") (pintype "input"))
      (node (ref "U1") (pin "D3") (pinfunction "TRSTN_D3") (pintype "bidirectional"))
    )
    (net (code "73") (name "/OSC.GND") (class "Default")
      (node (ref "C2") (pin "1") (pinfunction "1_1") (pintype "bidirectional"))
      (node (ref "C3") (pin "1") (pinfunction "1_1") (pintype "bidirectional"))
      (node (ref "U1") (pin "N15") (pinfunction "OSC0_GND_N15") (pintype "bidirectional"))
    )
    (net (code "74") (name "/OSC.IN") (class "Default")
      (node (ref "C2") (pin "2") (pinfunction "2_2") (pintype "bidirectional"))
      (node (ref "R2") (pin "2") (pinfunction "2_2") (pintype "bidirectional"))
      (node (ref "U1") (pin "P16") (pinfunction "OSC0_IN_P16") (pintype "bidirectional"))
      (node (ref "Y1") (pin "2") (pinfunction "P$2_2") (pintype "passive"))
    )
    (net (code "75") (name "/OSC.OUT") (class "Default")
      (node (ref "C3") (pin "2") (pinfunction "2_2") (pintype "bidirectional"))
      (node (ref "R2") (pin "1") (pinfunction "1_1") (pintype "bidirectional"))
      (node (ref "U1") (pin "N16") (pinfunction "OSC0_OUT_N16") (pintype "bidirectional"))
      (node (ref "Y1") (pin "1") (pinfunction "P$1_1") (pintype "passive"))
    )
    (net (code "76") (name "/PMIC_PGOOD") (class "Default")
      (node (ref "U1") (pin "N12") (pinfunction "PMIC_PGOOD_N12") (pintype "output"))
      (node (ref "U1") (pin "P11") (pinfunction "PWRONRSTN_P11") (pintype "bidirectional"))
      (node (ref "U2") (pin "2") (pinfunction "A_2") (pintype "bidirectional"))
    )
    (net (code "77") (name "/PRU0.1") (class "Default")
      (node (ref "P1") (pin "33") (pinfunction "33_33") (pintype "bidirectional"))
      (node (ref "U1") (pin "A2") (pinfunction "MCASP0_FSX_A2") (pintype "bidirectional"))
    )
    (net (code "78") (name "/PRU0.2") (class "Default")
      (node (ref "P2") (pin "32") (pinfunction "32_32") (pintype "bidirectional"))
      (node (ref "U1") (pin "B2") (pinfunction "MCASP0_AXR0_B2") (pintype "bidirectional"))
    )
    (net (code "79") (name "/PRU0.3") (class "Default")
      (node (ref "P2") (pin "30") (pinfunction "30_30") (pintype "bidirectional"))
      (node (ref "U1") (pin "B1") (pinfunction "MCASP0_AHCLKR_B1") (pintype "bidirectional"))
    )
    (net (code "80") (name "/PRU0.4") (class "Default")
      (node (ref "P1") (pin "31") (pinfunction "31_31") (pintype "bidirectional"))
      (node (ref "U1") (pin "A3") (pinfunction "MCASP0_ACLKR_A3") (pintype "bidirectional"))
    )
    (net (code "81") (name "/PRU0.5") (class "Default")
      (node (ref "P2") (pin "34") (pinfunction "34_34") (pintype "bidirectional"))
      (node (ref "U1") (pin "B3") (pinfunction "MCASP0_FSR_B3") (pintype "bidirectional"))
    )
    (net (code "82") (name "/PRU0.6") (class "Default")
      (node (ref "P2") (pin "28") (pinfunction "28_28") (pintype "bidirectional"))
      (node (ref "U1") (pin "C3") (pinfunction "MCASP0_AXR1_C3") (pintype "bidirectional"))
    )
    (net (code "83") (name "/PRU0.7") (class "Default")
      (node (ref "P1") (pin "29") (pinfunction "29_29") (pintype "bidirectional"))
      (node (ref "U1") (pin "C4") (pinfunction "MCASP0_AHCLKX_C4") (pintype "bidirectional"))
    )
    (net (code "84") (name "/PRU1.10") (class "Default")
      (node (ref "P1") (pin "35") (pinfunction "35_35") (pintype "bidirectional"))
      (node (ref "U1") (pin "F1") (pinfunction "LCD_PCLK_F1") (pintype "bidirectional"))
    )
    (net (code "85") (name "/PWM0A") (class "Default")
      (node (ref "P1") (pin "36") (pinfunction "36_36") (pintype "bidirectional"))
      (node (ref "U1") (pin "A1") (pinfunction "MCASP0_ACLKX_A1") (pintype "bidirectional"))
    )
    (net (code "86") (name "/PWM1A") (class "Default")
      (node (ref "P2") (pin "1") (pinfunction "1_1") (pintype "bidirectional"))
      (node (ref "U1") (pin "P12") (pinfunction "GPMC_A2_P12") (pintype "bidirectional"))
    )
    (net (code "87") (name "/PWR.BTN") (class "Default")
      (node (ref "P2") (pin "12") (pinfunction "12_12") (pintype "bidirectional"))
      (node (ref "POWER") (pin "3") (pinfunction "3_3") (pintype "bidirectional"))
      (node (ref "POWER") (pin "4") (pinfunction "4_4") (pintype "bidirectional"))
      (node (ref "U1") (pin "T11") (pinfunction "PMIC_PB_IN_T11") (pintype "bidirectional"))
    )
    (net (code "88") (name "/RESET#") (class "Default")
      (node (ref "P2") (pin "26") (pinfunction "26_26") (pintype "bidirectional"))
      (node (ref "U1") (pin "R11") (pinfunction "WARMRSTN_R11") (pintype "bidirectional"))
      (node (ref "U2") (pin "4") (pinfunction "Y_4") (pintype "bidirectional"))
    )
    (net (code "89") (name "/SPI0.CLK") (class "Default")
      (node (ref "P1") (pin "8") (pinfunction "8_8") (pintype "bidirectional"))
      (node (ref "U1") (pin "A13") (pinfunction "SPI0_SCLK_A13") (pintype "bidirectional"))
    )
    (net (code "90") (name "/SPI0.CS") (class "Default")
      (node (ref "P1") (pin "6") (pinfunction "6_6") (pintype "bidirectional"))
      (node (ref "U1") (pin "A14") (pinfunction "SPI0_CS0_A14") (pintype "bidirectional"))
    )
    (net (code "91") (name "/SPI0.MISO") (class "Default")
      (node (ref "P1") (pin "10") (pinfunction "10_10") (pintype "bidirectional"))
      (node (ref "U1") (pin "B13") (pinfunction "SPI0_D0_B13") (pintype "bidirectional"))
    )
    (net (code "92") (name "/SPI0.MOSI") (class "Default")
      (node (ref "P1") (pin "12") (pinfunction "12_12") (pintype "bidirectional"))
      (node (ref "U1") (pin "B14") (pinfunction "SPI0_D1_B14") (pintype "bidirectional"))
    )
    (net (code "93") (name "/SPI1.CLK") (class "Default")
      (node (ref "P2") (pin "29") (pinfunction "29_29") (pintype "bidirectional"))
      (node (ref "U1") (pin "C5") (pinfunction "ECAP0_IN_PWM0_OUT_C5") (pintype "bidirectional"))
    )
    (net (code "94") (name "/SPI1.CS") (class "Default")
      (node (ref "P2") (pin "31") (pinfunction "31_31") (pintype "bidirectional"))
      (node (ref "U1") (pin "A4") (pinfunction "XDMA_EVENT_INTR0_A4") (pintype "bidirectional"))
    )
    (net (code "95") (name "/SPI1.MISO") (class "Default")
      (node (ref "P2") (pin "27") (pinfunction "27_27") (pintype "bidirectional"))
      (node (ref "U1") (pin "C12") (pinfunction "UART0_CTSN_C12") (pintype "bidirectional"))
    )
    (net (code "96") (name "/SPI1.MOSI") (class "Default")
      (node (ref "P2") (pin "25") (pinfunction "25_25") (pintype "bidirectional"))
      (node (ref "U1") (pin "C13") (pinfunction "UART0_RTSN_C13") (pintype "bidirectional"))
    )
    (net (code "97") (name "/UART0.RX") (class "Default")
      (node (ref "P1") (pin "32") (pinfunction "32_32") (pintype "bidirectional"))
      (node (ref "U1") (pin "A12") (pinfunction "UART0_RXD_A12") (pintype "bidirectional"))
    )
    (net (code "98") (name "/UART0.TX") (class "Default")
      (node (ref "P1") (pin "30") (pinfunction "30_30") (pintype "bidirectional"))
      (node (ref "U1") (pin "B12") (pinfunction "UART0_TXD_B12") (pintype "bidirectional"))
    )
    (net (code "99") (name "/UART4.RX") (class "Default")
      (node (ref "P2") (pin "5") (pinfunction "5_5") (pintype "bidirectional"))
      (node (ref "U1") (pin "P15") (pinfunction "GPMC_WAIT0_P15") (pintype "bidirectional"))
    )
    (net (code "100") (name "/UART4.TX") (class "Default")
      (node (ref "P2") (pin "7") (pinfunction "7_7") (pintype "bidirectional"))
      (node (ref "U1") (pin "R16") (pinfunction "GPMC_WPN_R16") (pintype "bidirectional"))
    )
    (net (code "101") (name "/USB1.D+") (class "Default")
      (node (ref "P1") (pin "11") (pinfunction "11_11") (pintype "bidirectional"))
      (node (ref "U1") (pin "L15") (pinfunction "USB1_DP_L15") (pintype "bidirectional"))
    )
    (net (code "102") (name "/USB1.D-") (class "Default")
      (node (ref "P1") (pin "9") (pinfunction "9_9") (pintype "bidirectional"))
      (node (ref "U1") (pin "L16") (pinfunction "USB1_DM_L16") (pintype "bidirectional"))
    )
    (net (code "103") (name "/USB1.DRVVBUS") (class "Default")
      (node (ref "P1") (pin "3") (pinfunction "3_3") (pintype "bidirectional"))
      (node (ref "U1") (pin "M14") (pinfunction "USB1_DRVVBUS_M14") (pintype "bidirectional"))
    )
    (net (code "104") (name "/USB1.ID") (class "Default")
      (node (ref "P1") (pin "13") (pinfunction "13_13") (pintype "bidirectional"))
      (node (ref "U1") (pin "L14") (pinfunction "USB1_ID_L14") (pintype "bidirectional"))
    )
    (net (code "105") (name "/USB1.VBUS") (class "Default")
      (node (ref "P1") (pin "5") (pinfunction "5_5") (pintype "bidirectional"))
      (node (ref "U1") (pin "M15") (pinfunction "USB1_VBUS_M15") (pintype "bidirectional"))
    )
    (net (code "106") (name "3.3V") (class "Default")
      (node (ref "C5") (pin "1") (pinfunction "1_1") (pintype "bidirectional"))
      (node (ref "C6") (pin "1") (pinfunction "1_1") (pintype "bidirectional"))
      (node (ref "P1") (pin "14") (pinfunction "14_14") (pintype "bidirectional"))
      (node (ref "P2") (pin "23") (pinfunction "23_23") (pintype "bidirectional"))
      (node (ref "R10") (pin "5") (pinfunction "5_5") (pintype "bidirectional"))
      (node (ref "R10") (pin "6") (pinfunction "6_6") (pintype "bidirectional"))
      (node (ref "R10") (pin "7") (pinfunction "7_7") (pintype "bidirectional"))
      (node (ref "R10") (pin "8") (pinfunction "8_8") (pintype "bidirectional"))
      (node (ref "R11") (pin "2") (pinfunction "2_2") (pintype "bidirectional"))
      (node (ref "R11") (pin "3") (pinfunction "3_3") (pintype "bidirectional"))
      (node (ref "R11") (pin "4") (pinfunction "4_4") (pintype "bidirectional"))
      (node (ref "R6") (pin "7") (pinfunction "7_7") (pintype "bidirectional"))
      (node (ref "R8") (pin "5") (pinfunction "5_5") (pintype "bidirectional"))
      (node (ref "R9") (pin "4") (pinfunction "4_4") (pintype "bidirectional"))
      (node (ref "U1") (pin "F6") (pinfunction "SYS_VDD1_3P3V_F6") (pintype "power_in"))
      (node (ref "U1") (pin "F7") (pinfunction "SYS_VDD1_3P3V_F7") (pintype "power_in"))
      (node (ref "U1") (pin "G6") (pinfunction "SYS_VDD1_3P3V_G6") (pintype "power_in"))
      (node (ref "U1") (pin "G7") (pinfunction "SYS_VDD1_3P3V_G7") (pintype "power_in"))
      (node (ref "X2") (pin "4") (pinfunction "VDD_4") (pintype "bidirectional"))
    )
    (net (code "107") (name "CGND") (class "Default")
      (node (ref "FB2") (pin "1") (pinfunction "P$1_1") (pintype "bidirectional"))
      (node (ref "X1") (pin "CGND1") (pinfunction "SGND1_CGND1") (pintype "bidirectional"))
      (node (ref "X1") (pin "CGND2") (pinfunction "SGND2_CGND2") (pintype "bidirectional"))
      (node (ref "X1") (pin "CGND3") (pinfunction "SGND3_CGND3") (pintype "bidirectional"))
      (node (ref "X1") (pin "CGND4") (pinfunction "SGND4_CGND4") (pintype "bidirectional"))
      (node (ref "X1") (pin "CGND5") (pinfunction "SGND5_CGND5") (pintype "bidirectional"))
      (node (ref "X1") (pin "CGND6") (pinfunction "SGND6_CGND6") (pintype "bidirectional"))
      (node (ref "X2") (pin "G1") (pinfunction "G1_G1") (pintype "bidirectional"))
      (node (ref "X2") (pin "G2") (pinfunction "G2_G2") (pintype "bidirectional"))
      (node (ref "X2") (pin "G3") (pinfunction "G3_G3") (pintype "bidirectional"))
      (node (ref "X2") (pin "G4") (pinfunction "G4_G4") (pintype "bidirectional"))
    )
    (net (code "108") (name "GND") (class "Default")
      (node (ref "C1") (pin "2") (pinfunction "2_2") (pintype "bidirectional"))
      (node (ref "C5") (pin "2") (pinfunction "2_2") (pintype "bidirectional"))
      (node (ref "C6") (pin "2") (pinfunction "2_2") (pintype "bidirectional"))
      (node (ref "D1") (pin "1") (pinfunction "1_1") (pintype "bidirectional"))
      (node (ref "D2") (pin "1") (pinfunction "1_1") (pintype "bidirectional"))
      (node (ref "D3") (pin "1") (pinfunction "1_1") (pintype "bidirectional"))
      (node (ref "D4") (pin "1") (pinfunction "1_1") (pintype "bidirectional"))
      (node (ref "FB2") (pin "2") (pinfunction "P$2_2") (pintype "bidirectional"))
      (node (ref "P1") (pin "15") (pinfunction "15_15") (pintype "bidirectional"))
      (node (ref "P1") (pin "16") (pinfunction "16_16") (pintype "bidirectional"))
      (node (ref "P1") (pin "22") (pinfunction "22_22") (pintype "bidirectional"))
      (node (ref "P2") (pin "15") (pinfunction "15_15") (pintype "bidirectional"))
      (node (ref "P2") (pin "21") (pinfunction "21_21") (pintype "bidirectional"))
      (node (ref "POWER") (pin "1") (pinfunction "1_1") (pintype "bidirectional"))
      (node (ref "POWER") (pin "2") (pinfunction "2_2") (pintype "bidirectional"))
      (node (ref "R1") (pin "1") (pinfunction "1_1") (pintype "bidirectional"))
      (node (ref "R12") (pin "1") (pinfunction "1_1") (pintype "bidirectional"))
      (node (ref "R3") (pin "1") (pinfunction "1_1") (pintype "bidirectional"))
      (node (ref "R4") (pin "5") (pinfunction "5_5") (pintype "bidirectional"))
      (node (ref "R4") (pin "6") (pinfunction "6_6") (pintype "bidirectional"))
      (node (ref "R4") (pin "7") (pinfunction "7_7") (pintype "bidirectional"))
      (node (ref "R4") (pin "8") (pinfunction "8_8") (pintype "bidirectional"))
      (node (ref "R5") (pin "5") (pinfunction "5_5") (pintype "bidirectional"))
      (node (ref "R5") (pin "8") (pinfunction "8_8") (pintype "bidirectional"))
      (node (ref "R6") (pin "5") (pinfunction "5_5") (pintype "bidirectional"))
      (node (ref "R6") (pin "6") (pinfunction "6_6") (pintype "bidirectional"))
      (node (ref "R6") (pin "8") (pinfunction "8_8") (pintype "bidirectional"))
      (node (ref "R7") (pin "5") (pinfunction "5_5") (pintype "bidirectional"))
      (node (ref "R7") (pin "6") (pinfunction "6_6") (pintype "bidirectional"))
      (node (ref "R7") (pin "7") (pinfunction "7_7") (pintype "bidirectional"))
      (node (ref "R7") (pin "8") (pinfunction "8_8") (pintype "bidirectional"))
      (node (ref "R8") (pin "6") (pinfunction "6_6") (pintype "bidirectional"))
      (node (ref "R8") (pin "7") (pinfunction "7_7") (pintype "bidirectional"))
      (node (ref "R8") (pin "8") (pinfunction "8_8") (pintype "bidirectional"))
      (node (ref "R9") (pin "1") (pinfunction "1_1") (pintype "bidirectional"))
      (node (ref "R9") (pin "2") (pinfunction "2_2") (pintype "bidirectional"))
      (node (ref "R9") (pin "3") (pinfunction "3_3") (pintype "bidirectional"))
      (node (ref "U1") (pin "D8") (pinfunction "DGND_D8") (pintype "bidirectional"))
      (node (ref "U1") (pin "D9") (pinfunction "DGND_D9") (pintype "bidirectional"))
      (node (ref "U1") (pin "E10") (pinfunction "DGND_E10") (pintype "bidirectional"))
      (node (ref "U1") (pin "E11") (pinfunction "DGND_E11") (pintype "bidirectional"))
      (node (ref "U1") (pin "E12") (pinfunction "DGND_E12") (pintype "bidirectional"))
      (node (ref "U1") (pin "E5") (pinfunction "DGND_E5") (pintype "bidirectional"))
      (node (ref "U1") (pin "E6") (pinfunction "DGND_E6") (pintype "bidirectional"))
      (node (ref "U1") (pin "E7") (pinfunction "DGND_E7") (pintype "bidirectional"))
      (node (ref "U1") (pin "E8") (pinfunction "DGND_E8") (pintype "bidirectional"))
      (node (ref "U1") (pin "E9") (pinfunction "DGND_E9") (pintype "bidirectional"))
      (node (ref "U1") (pin "F12") (pinfunction "DGND_F12") (pintype "bidirectional"))
      (node (ref "U1") (pin "F5") (pinfunction "DGND_F5") (pintype "bidirectional"))
      (node (ref "U1") (pin "G12") (pinfunction "DGND_G12") (pintype "bidirectional"))
      (node (ref "U1") (pin "G5") (pinfunction "DGND_G5") (pintype "bidirectional"))
      (node (ref "U1") (pin "H12") (pinfunction "DGND_H12") (pintype "bidirectional"))
      (node (ref "U1") (pin "H13") (pinfunction "DGND_H13") (pintype "bidirectional"))
      (node (ref "U1") (pin "H4") (pinfunction "DGND_H4") (pintype "bidirectional"))
      (node (ref "U1") (pin "H5") (pinfunction "DGND_H5") (pintype "bidirectional"))
      (node (ref "U1") (pin "J12") (pinfunction "DGND_J12") (pintype "bidirectional"))
      (node (ref "U1") (pin "J13") (pinfunction "DGND_J13") (pintype "bidirectional"))
      (node (ref "U1") (pin "J4") (pinfunction "DGND_J4") (pintype "bidirectional"))
      (node (ref "U1") (pin "J5") (pinfunction "DGND_J5") (pintype "bidirectional"))
      (node (ref "U1") (pin "K12") (pinfunction "DGND_K12") (pintype "bidirectional"))
      (node (ref "U1") (pin "K5") (pinfunction "DGND_K5") (pintype "bidirectional"))
      (node (ref "U1") (pin "L12") (pinfunction "DGND_L12") (pintype "bidirectional"))
      (node (ref "U1") (pin "L5") (pinfunction "DGND_L5") (pintype "bidirectional"))
      (node (ref "U1") (pin "M10") (pinfunction "DGND_M10") (pintype "bidirectional"))
      (node (ref "U1") (pin "M11") (pinfunction "DGND_M11") (pintype "bidirectional"))
      (node (ref "U1") (pin "M12") (pinfunction "DGND_M12") (pintype "bidirectional"))
      (node (ref "U1") (pin "M5") (pinfunction "DGND_M5") (pintype "bidirectional"))
      (node (ref "U1") (pin "M6") (pinfunction "DGND_M6") (pintype "bidirectional"))
      (node (ref "U1") (pin "M7") (pinfunction "DGND_M7") (pintype "bidirectional"))
      (node (ref "U1") (pin "M8") (pinfunction "DGND_M8") (pintype "bidirectional"))
      (node (ref "U1") (pin "M9") (pinfunction "DGND_M9") (pintype "bidirectional"))
      (node (ref "U1") (pin "N8") (pinfunction "DGND_N8") (pintype "bidirectional"))
      (node (ref "U1") (pin "N9") (pinfunction "DGND_N9") (pintype "bidirectional"))
      (node (ref "U2") (pin "3") (pinfunction "GND_3") (pintype "bidirectional"))
      (node (ref "X1") (pin "GND") (pinfunction "GND_GND") (pintype "input"))
      (node (ref "X2") (pin "6") (pinfunction "VSS_6") (pintype "bidirectional"))
    )
    (net (code "109") (name "Net-(FB1-P$1)") (class "Default")
      (node (ref "FB1") (pin "1") (pinfunction "P$1_1") (pintype "bidirectional"))
      (node (ref "X1") (pin "VBUS") (pinfunction "VBUS_VBUS") (pintype "input"))
    )
    (net (code "110") (name "Net-(PWR-PadK)") (class "Default")
      (node (ref "PWR") (pin "K") (pinfunction "K_K") (pintype "passive"))
      (node (ref "R1") (pin "2") (pinfunction "2_2") (pintype "bidirectional"))
    )
    (net (code "111") (name "Net-(R4-Pad1)") (class "Default")
      (node (ref "R4") (pin "1") (pinfunction "1_1") (pintype "bidirectional"))
      (node (ref "USR0") (pin "K") (pinfunction "K_K") (pintype "passive"))
    )
    (net (code "112") (name "Net-(R4-Pad2)") (class "Default")
      (node (ref "R4") (pin "2") (pinfunction "2_2") (pintype "bidirectional"))
      (node (ref "USR1") (pin "K") (pinfunction "K_K") (pintype "passive"))
    )
    (net (code "113") (name "Net-(R4-Pad3)") (class "Default")
      (node (ref "R4") (pin "3") (pinfunction "3_3") (pintype "bidirectional"))
      (node (ref "USR2") (pin "K") (pinfunction "K_K") (pintype "passive"))
    )
    (net (code "114") (name "Net-(R4-Pad4)") (class "Default")
      (node (ref "R4") (pin "4") (pinfunction "4_4") (pintype "bidirectional"))
      (node (ref "USR3") (pin "K") (pinfunction "K_K") (pintype "passive"))
    )
    (net (code "115") (name "Net-(U1A-EXTINTN)") (class "Default")
      (node (ref "U1") (pin "D4") (pinfunction "EXTINTN_D4") (pintype "bidirectional"))
      (node (ref "U1") (pin "E4") (pinfunction "PMIC_NINT_E4") (pintype "output"))
    )
    (net (code "116") (name "Net-(U1A-EXT_WAKEUP)") (class "Default")
      (node (ref "U1") (pin "L4") (pinfunction "PMIC_NWAKEUP_L4") (pintype "output"))
      (node (ref "U1") (pin "M4") (pinfunction "EXT_WAKEUP_M4") (pintype "bidirectional"))
    )
    (net (code "117") (name "Net-(U1A-I2C0_SCL)") (class "Default")
      (node (ref "U1") (pin "C10") (pinfunction "I2C0_SCL_C10") (pintype "bidirectional"))
      (node (ref "U1") (pin "D10") (pinfunction "PMIC_SCL_D10") (pintype "bidirectional"))
    )
    (net (code "118") (name "Net-(U1A-I2C0_SDA)") (class "Default")
      (node (ref "U1") (pin "C11") (pinfunction "I2C0_SDA_C11") (pintype "bidirectional"))
      (node (ref "U1") (pin "D11") (pinfunction "PMIC_SDA_D11") (pintype "bidirectional"))
    )
    (net (code "119") (name "Net-(U1A-PMIC_LDO_PGOOD)") (class "Default")
      (node (ref "U1") (pin "N4") (pinfunction "PMIC_LDO_PGOOD_N4") (pintype "output"))
      (node (ref "U1") (pin "N5") (pinfunction "RTC_PWRONRSTN_N5") (pintype "bidirectional"))
    )
    (net (code "120") (name "Net-(U1A-PMIC_POWER_EN)") (class "Default")
      (node (ref "U1") (pin "N10") (pinfunction "PMIC_POWER_EN_N10") (pintype "output"))
      (node (ref "U1") (pin "N11") (pinfunction "PMIC_PWR_EN_N11") (pintype "input"))
    )
    (net (code "121") (name "Net-(U1A-RTC_KALDO_ENN)") (class "Default")
      (node (ref "R3") (pin "2") (pinfunction "2_2") (pintype "bidirectional"))
      (node (ref "U1") (pin "M16") (pinfunction "RTC_KALDO_ENN_M16") (pintype "bidirectional"))
    )
    (net (code "122") (name "Net-(U1B-AIN7)") (class "Default")
      (node (ref "U1") (pin "D6") (pinfunction "PMIC_MUX_OUT_D6") (pintype "bidirectional"))
      (node (ref "U1") (pin "D7") (pinfunction "AIN7_D7") (pintype "bidirectional"))
    )
    (net (code "123") (name "Net-(U1F-VDDS_DDR)") (class "Default")
      (node (ref "TP1") (pin "TP") (pinfunction "TP_TP") (pintype "input"))
      (node (ref "U1") (pin "F4") (pinfunction "VDDS_DDR_F4") (pintype "bidirectional"))
    )
    (net (code "124") (name "Net-(U1F-VDDS_PLL)") (class "Default")
      (node (ref "TP4") (pin "TP") (pinfunction "TP_TP") (pintype "input"))
      (node (ref "U1") (pin "G13") (pinfunction "VDDS_PLL_G13") (pintype "bidirectional"))
    )
    (net (code "125") (name "Net-(U1F-VDD_CORE)") (class "Default")
      (node (ref "TP2") (pin "TP") (pinfunction "TP_TP") (pintype "input"))
      (node (ref "U1") (pin "G4") (pinfunction "VDD_CORE_G4") (pintype "bidirectional"))
    )
    (net (code "126") (name "Net-(U1F-VDD_MPU)") (class "Default")
      (node (ref "TP3") (pin "TP") (pinfunction "TP_TP") (pintype "input"))
      (node (ref "U1") (pin "F13") (pinfunction "VDD_MPU_F13") (pintype "bidirectional"))
    )
    (net (code "127") (name "USB1.VIN") (class "Default")
      (node (ref "D3") (pin "2") (pinfunction "2_2") (pintype "bidirectional"))
      (node (ref "FB1") (pin "2") (pinfunction "P$2_2") (pintype "bidirectional"))
      (node (ref "P1") (pin "7") (pinfunction "7_7") (pintype "bidirectional"))
      (node (ref "U1") (pin "J16") (pinfunction "USB0_VBUS_J16") (pintype "bidirectional"))
      (node (ref "U1") (pin "P9") (pinfunction "VIN_USB_P9") (pintype "power_in"))
      (node (ref "U1") (pin "R9") (pinfunction "VIN_USB_R9") (pintype "power_in"))
      (node (ref "U1") (pin "T9") (pinfunction "VIN_USB_T9") (pintype "power_in"))
    )
    (net (code "128") (name "VDD_1V8") (class "Default")
      (node (ref "U1") (pin "F10") (pinfunction "SYS_VDD_1P8V_F10") (pintype "power_in"))
      (node (ref "U1") (pin "G10") (pinfunction "SYS_VDD_1P8V_G10") (pintype "power_in"))
      (node (ref "U1") (pin "H10") (pinfunction "SYS_VDD_1P8V_H10") (pintype "power_in"))
      (node (ref "U1") (pin "H11") (pinfunction "SYS_VDD_1P8V_H11") (pintype "power_in"))
      (node (ref "U1") (pin "J10") (pinfunction "SYS_VDD_1P8V_J10") (pintype "power_in"))
      (node (ref "U1") (pin "J11") (pinfunction "SYS_VDD_1P8V_J11") (pintype "power_in"))
      (node (ref "U1") (pin "K10") (pinfunction "SYS_VDD_1P8V_K10") (pintype "power_in"))
      (node (ref "U1") (pin "L10") (pinfunction "SYS_VDD_1P8V_L10") (pintype "power_in"))
    )
    (net (code "129") (name "VDD_3V3A") (class "Default")
      (node (ref "U1") (pin "F8") (pinfunction "SYS_VDD3_3P3V_F8") (pintype "power_in"))
      (node (ref "U1") (pin "F9") (pinfunction "VDDSHV4_F9") (pintype "power_in"))
      (node (ref "U1") (pin "G8") (pinfunction "SYS_VDD3_3P3V_G8") (pintype "power_in"))
      (node (ref "U1") (pin "G9") (pinfunction "VDDSHV5_G9") (pintype "power_in"))
      (node (ref "U1") (pin "H7") (pinfunction "SYS_VDD3_3P3V_H7") (pintype "power_in"))
      (node (ref "U1") (pin "H8") (pinfunction "SYS_VDD3_3P3V_H8") (pintype "power_in"))
      (node (ref "U1") (pin "H9") (pinfunction "VDDSHV6_H9") (pintype "power_in"))
      (node (ref "U1") (pin "J7") (pinfunction "SYS_VDD3_3P3V_J7") (pintype "power_in"))
      (node (ref "U1") (pin "J8") (pinfunction "SYS_VDD3_3P3V_J8") (pintype "power_in"))
      (node (ref "U1") (pin "J9") (pinfunction "VDDSHV1_J9") (pintype "power_in"))
      (node (ref "U1") (pin "K8") (pinfunction "SYS_VDD3_3P3V_K8") (pintype "power_in"))
      (node (ref "U1") (pin "K9") (pinfunction "VDDSHV2_K9") (pintype "power_in"))
      (node (ref "U1") (pin "L8") (pinfunction "SYS_VDD3_3P3V_L8") (pintype "power_in"))
      (node (ref "U1") (pin "L9") (pinfunction "VDDSHV3_L9") (pintype "power_in"))
    )
    (net (code "130") (name "VDD_3V3AUX") (class "Default")
      (node (ref "PWR") (pin "A") (pinfunction "A_A") (pintype "passive"))
      (node (ref "U1") (pin "F11") (pinfunction "SYS_VDD2_3P3V_F11") (pintype "power_in"))
      (node (ref "U1") (pin "G11") (pinfunction "SYS_VDD2_3P3V_G11") (pintype "power_in"))
    )
    (net (code "131") (name "VDD_RTC") (class "Default")
      (node (ref "C1") (pin "1") (pinfunction "1_1") (pintype "bidirectional"))
      (node (ref "U1") (pin "K11") (pinfunction "SYS_RTC_1P8V_K11") (pintype "power_in"))
      (node (ref "U1") (pin "L11") (pinfunction "SYS_RTC_1P8V_L11") (pintype "power_in"))
      (node (ref "U2") (pin "5") (pinfunction "VCC_5") (pintype "bidirectional"))
    )
    (net (code "132") (name "VIN") (class "Default")
      (node (ref "P1") (pin "1") (pinfunction "1_1") (pintype "bidirectional"))
      (node (ref "U1") (pin "P10") (pinfunction "VIN_AC_P10") (pintype "power_in"))
      (node (ref "U1") (pin "R10") (pinfunction "VIN_AC_R10") (pintype "power_in"))
      (node (ref "U1") (pin "T10") (pinfunction "VIN_AC_T10") (pintype "power_in"))
    )
    (net (code "133") (name "VOUT") (class "Default")
      (node (ref "P1") (pin "24") (pinfunction "24_24") (pintype "bidirectional"))
      (node (ref "P2") (pin "13") (pinfunction "13_13") (pintype "bidirectional"))
      (node (ref "U1") (pin "K6") (pinfunction "SYS_VOUT_K6") (pintype "power_in"))
      (node (ref "U1") (pin "K7") (pinfunction "SYS_VOUT_K7") (pintype "power_in"))
      (node (ref "U1") (pin "L6") (pinfunction "SYS_VOUT_L6") (pintype "power_in"))
      (node (ref "U1") (pin "L7") (pinfunction "SYS_VOUT_L7") (pintype "power_in"))
    )
    (net (code "134") (name "unconnected-(FUD1-PadP$1)") (class "Default")
      (node (ref "FUD1") (pin "P$1") (pinfunction "P$1_P$1") (pintype "no_connect"))
    )
    (net (code "135") (name "unconnected-(FUD2-PadP$1)") (class "Default")
      (node (ref "FUD2") (pin "P$1") (pinfunction "P$1_P$1") (pintype "no_connect"))
    )
    (net (code "136") (name "unconnected-(FUD3-PadP$1)") (class "Default")
      (node (ref "FUD3") (pin "P$1") (pinfunction "P$1_P$1") (pintype "no_connect"))
    )
    (net (code "137") (name "unconnected-(R11-Pad1)") (class "Default")
      (node (ref "R11") (pin "1") (pinfunction "1_1") (pintype "bidirectional"))
    )
    (net (code "138") (name "unconnected-(R11-Pad8)") (class "Default")
      (node (ref "R11") (pin "8") (pinfunction "8_8") (pintype "bidirectional"))
    )
    (net (code "139") (name "unconnected-(U1A-PMIC_NRESET-PadM13)") (class "Default")
      (node (ref "U1") (pin "M13") (pinfunction "PMIC_NRESET_M13") (pintype "bidirectional"))
    )
    (net (code "140") (name "unconnected-(U1B-OSC1_GND-PadB5)") (class "Default")
      (node (ref "U1") (pin "B5") (pinfunction "OSC1_GND_B5") (pintype "bidirectional"))
    )
    (net (code "141") (name "unconnected-(U1B-OSC1_IN-PadA6)") (class "Default")
      (node (ref "U1") (pin "A6") (pinfunction "OSC1_IN_A6") (pintype "bidirectional"))
    )
    (net (code "142") (name "unconnected-(U1B-OSC1_OUT-PadA5)") (class "Default")
      (node (ref "U1") (pin "A5") (pinfunction "OSC1_OUT_A5") (pintype "bidirectional"))
    )
    (net (code "143") (name "unconnected-(U1B-USB0_CE-PadK13)") (class "Default")
      (node (ref "U1") (pin "K13") (pinfunction "USB0_CE_K13") (pintype "bidirectional"))
    )
    (net (code "144") (name "unconnected-(U1B-USB0_DRVVBUS-PadJ15)") (class "Default")
      (node (ref "U1") (pin "J15") (pinfunction "USB0_DRVVBUS_J15") (pintype "bidirectional"))
    )
    (net (code "145") (name "unconnected-(U1B-USB1_CE-PadL13)") (class "Default")
      (node (ref "U1") (pin "L13") (pinfunction "USB1_CE_L13") (pintype "bidirectional"))
    )
    (net (code "146") (name "unconnected-(U1C-GPMC_A0-PadT12)") (class "Default")
      (node (ref "U1") (pin "T12") (pinfunction "GPMC_A0_T12") (pintype "bidirectional"))
    )
    (net (code "147") (name "unconnected-(U1C-GPMC_A1-PadR12)") (class "Default")
      (node (ref "U1") (pin "R12") (pinfunction "GPMC_A1_R12") (pintype "bidirectional"))
    )
    (net (code "148") (name "unconnected-(U1C-GPMC_A3-PadT13)") (class "Default")
      (node (ref "U1") (pin "T13") (pinfunction "GPMC_A3_T13") (pintype "bidirectional"))
    )
    (net (code "149") (name "unconnected-(U1C-GPMC_AD0-PadR3)") (class "Default")
      (node (ref "U1") (pin "R3") (pinfunction "GPMC_AD0_R3") (pintype "bidirectional"))
    )
    (net (code "150") (name "unconnected-(U1C-GPMC_AD1-PadR2)") (class "Default")
      (node (ref "U1") (pin "R2") (pinfunction "GPMC_AD1_R2") (pintype "bidirectional"))
    )
    (net (code "151") (name "unconnected-(U1C-GPMC_AD2-PadR1)") (class "Default")
      (node (ref "U1") (pin "R1") (pinfunction "GPMC_AD2_R1") (pintype "bidirectional"))
    )
    (net (code "152") (name "unconnected-(U1C-GPMC_AD3-PadT3)") (class "Default")
      (node (ref "U1") (pin "T3") (pinfunction "GPMC_AD3_T3") (pintype "bidirectional"))
    )
    (net (code "153") (name "unconnected-(U1C-GPMC_AD4-PadT2)") (class "Default")
      (node (ref "U1") (pin "T2") (pinfunction "GPMC_AD4_T2") (pintype "bidirectional"))
    )
    (net (code "154") (name "unconnected-(U1C-GPMC_AD5-PadT1)") (class "Default")
      (node (ref "U1") (pin "T1") (pinfunction "GPMC_AD5_T1") (pintype "bidirectional"))
    )
    (net (code "155") (name "unconnected-(U1C-GPMC_AD6-PadP4)") (class "Default")
      (node (ref "U1") (pin "P4") (pinfunction "GPMC_AD6_P4") (pintype "bidirectional"))
    )
    (net (code "156") (name "unconnected-(U1C-GPMC_AD7-PadR4)") (class "Default")
      (node (ref "U1") (pin "R4") (pinfunction "GPMC_AD7_R4") (pintype "bidirectional"))
    )
    (net (code "157") (name "unconnected-(U1C-GPMC_AD8-PadT4)") (class "Default")
      (node (ref "U1") (pin "T4") (pinfunction "GPMC_AD8_T4") (pintype "bidirectional"))
    )
    (net (code "158") (name "unconnected-(U1C-GPMC_ADVN_ALE-PadM1)") (class "Default")
      (node (ref "U1") (pin "M1") (pinfunction "GPMC_ADVN_ALE_M1") (pintype "bidirectional"))
    )
    (net (code "159") (name "unconnected-(U1C-GPMC_CSN0-PadP3)") (class "Default")
      (node (ref "U1") (pin "P3") (pinfunction "GPMC_CSN0_P3") (pintype "bidirectional"))
    )
    (net (code "160") (name "unconnected-(U1C-GPMC_CSN1-PadP2)") (class "Default")
      (node (ref "U1") (pin "P2") (pinfunction "GPMC_CSN1_P2") (pintype "bidirectional"))
    )
    (net (code "161") (name "unconnected-(U1C-GPMC_CSN2-PadP1)") (class "Default")
      (node (ref "U1") (pin "P1") (pinfunction "GPMC_CSN2_P1") (pintype "bidirectional"))
    )
    (net (code "162") (name "unconnected-(U1C-GPMC_OEN_REN-PadN1)") (class "Default")
      (node (ref "U1") (pin "N1") (pinfunction "GPMC_OEN_REN_N1") (pintype "bidirectional"))
    )
    (net (code "163") (name "unconnected-(U1C-GPMC_WEN-PadN2)") (class "Default")
      (node (ref "U1") (pin "N2") (pinfunction "GPMC_WEN_N2") (pintype "bidirectional"))
    )
    (net (code "164") (name "unconnected-(U1D-MDC-PadD13)") (class "Default")
      (node (ref "U1") (pin "D13") (pinfunction "MDC_D13") (pintype "bidirectional"))
    )
    (net (code "165") (name "unconnected-(U1D-MDIO-PadE13)") (class "Default")
      (node (ref "U1") (pin "E13") (pinfunction "MDIO_E13") (pintype "bidirectional"))
    )
    (net (code "166") (name "unconnected-(U1D-MII1_COL-PadF15)") (class "Default")
      (node (ref "U1") (pin "F15") (pinfunction "MII1_COL_F15") (pintype "bidirectional"))
    )
    (net (code "167") (name "unconnected-(U1D-MII1_CRS-PadF14)") (class "Default")
      (node (ref "U1") (pin "F14") (pinfunction "MII1_CRS_F14") (pintype "bidirectional"))
    )
    (net (code "168") (name "unconnected-(U1D-MII1_RXD0-PadE14)") (class "Default")
      (node (ref "U1") (pin "E14") (pinfunction "MII1_RXD0_E14") (pintype "bidirectional"))
    )
    (net (code "169") (name "unconnected-(U1D-MII1_RXD1-PadD16)") (class "Default")
      (node (ref "U1") (pin "D16") (pinfunction "MII1_RXD1_D16") (pintype "bidirectional"))
    )
    (net (code "170") (name "unconnected-(U1D-MII1_RXD2-PadD15)") (class "Default")
      (node (ref "U1") (pin "D15") (pinfunction "MII1_RXD2_D15") (pintype "bidirectional"))
    )
    (net (code "171") (name "unconnected-(U1D-MII1_RXD3-PadD14)") (class "Default")
      (node (ref "U1") (pin "D14") (pinfunction "MII1_RXD3_D14") (pintype "bidirectional"))
    )
    (net (code "172") (name "unconnected-(U1D-MII1_RX_CLK-PadE16)") (class "Default")
      (node (ref "U1") (pin "E16") (pinfunction "MII1_RX_CLK_E16") (pintype "bidirectional"))
    )
    (net (code "173") (name "unconnected-(U1D-MII1_RX_DV-PadF16)") (class "Default")
      (node (ref "U1") (pin "F16") (pinfunction "MII1_RX_DV_F16") (pintype "bidirectional"))
    )
    (net (code "174") (name "unconnected-(U1D-MII1_RX_ER-PadE15)") (class "Default")
      (node (ref "U1") (pin "E15") (pinfunction "MII1_RX_ER_E15") (pintype "bidirectional"))
    )
    (net (code "175") (name "unconnected-(U1D-MII1_TXD0-PadH15)") (class "Default")
      (node (ref "U1") (pin "H15") (pinfunction "MII1_TXD0_H15") (pintype "bidirectional"))
    )
    (net (code "176") (name "unconnected-(U1D-MII1_TXD1-PadH14)") (class "Default")
      (node (ref "U1") (pin "H14") (pinfunction "MII1_TXD1_H14") (pintype "bidirectional"))
    )
    (net (code "177") (name "unconnected-(U1D-MII1_TXD2-PadG16)") (class "Default")
      (node (ref "U1") (pin "G16") (pinfunction "MII1_TXD2_G16") (pintype "bidirectional"))
    )
    (net (code "178") (name "unconnected-(U1D-MII1_TXD3-PadG15)") (class "Default")
      (node (ref "U1") (pin "G15") (pinfunction "MII1_TXD3_G15") (pintype "bidirectional"))
    )
    (net (code "179") (name "unconnected-(U1D-MII1_TX_CLK-PadH16)") (class "Default")
      (node (ref "U1") (pin "H16") (pinfunction "MII1_TX_CLK_H16") (pintype "bidirectional"))
    )
    (net (code "180") (name "unconnected-(U1D-MII1_TX_EN-PadG14)") (class "Default")
      (node (ref "U1") (pin "G14") (pinfunction "MII1_TX_EN_G14") (pintype "bidirectional"))
    )
    (net (code "181") (name "unconnected-(U1D-RMII1_REF_CLK-PadJ14)") (class "Default")
      (node (ref "U1") (pin "J14") (pinfunction "RMII1_REF_CLK_J14") (pintype "bidirectional"))
    )
    (net (code "182") (name "unconnected-(U1F-CAP_VDD_RTC-PadD5)") (class "Default")
      (node (ref "U1") (pin "D5") (pinfunction "CAP_VDD_RTC_D5") (pintype "bidirectional"))
    )
    (net (code "183") (name "unconnected-(U1F-NC-PadD12)") (class "Default")
      (node (ref "U1") (pin "D12") (pinfunction "NC_D12") (pintype "bidirectional"))
    )
    (net (code "184") (name "unconnected-(U1F-NC-PadJ6)") (class "Default")
      (node (ref "U1") (pin "J6") (pinfunction "NC_J6") (pintype "bidirectional"))
    )
    (net (code "185") (name "unconnected-(U1F-NC-PadK4)") (class "Default")
      (node (ref "U1") (pin "K4") (pinfunction "NC_K4") (pintype "bidirectional"))
    )
    (net (code "186") (name "unconnected-(U1F-VPP-PadH6)") (class "Default")
      (node (ref "U1") (pin "H6") (pinfunction "VPP_H6") (pintype "bidirectional"))
    )
  )
)
